# Servosolenoidvalve_of_Tatebayashi.net
KiCad netlist of a schematic drawn in EAGLE
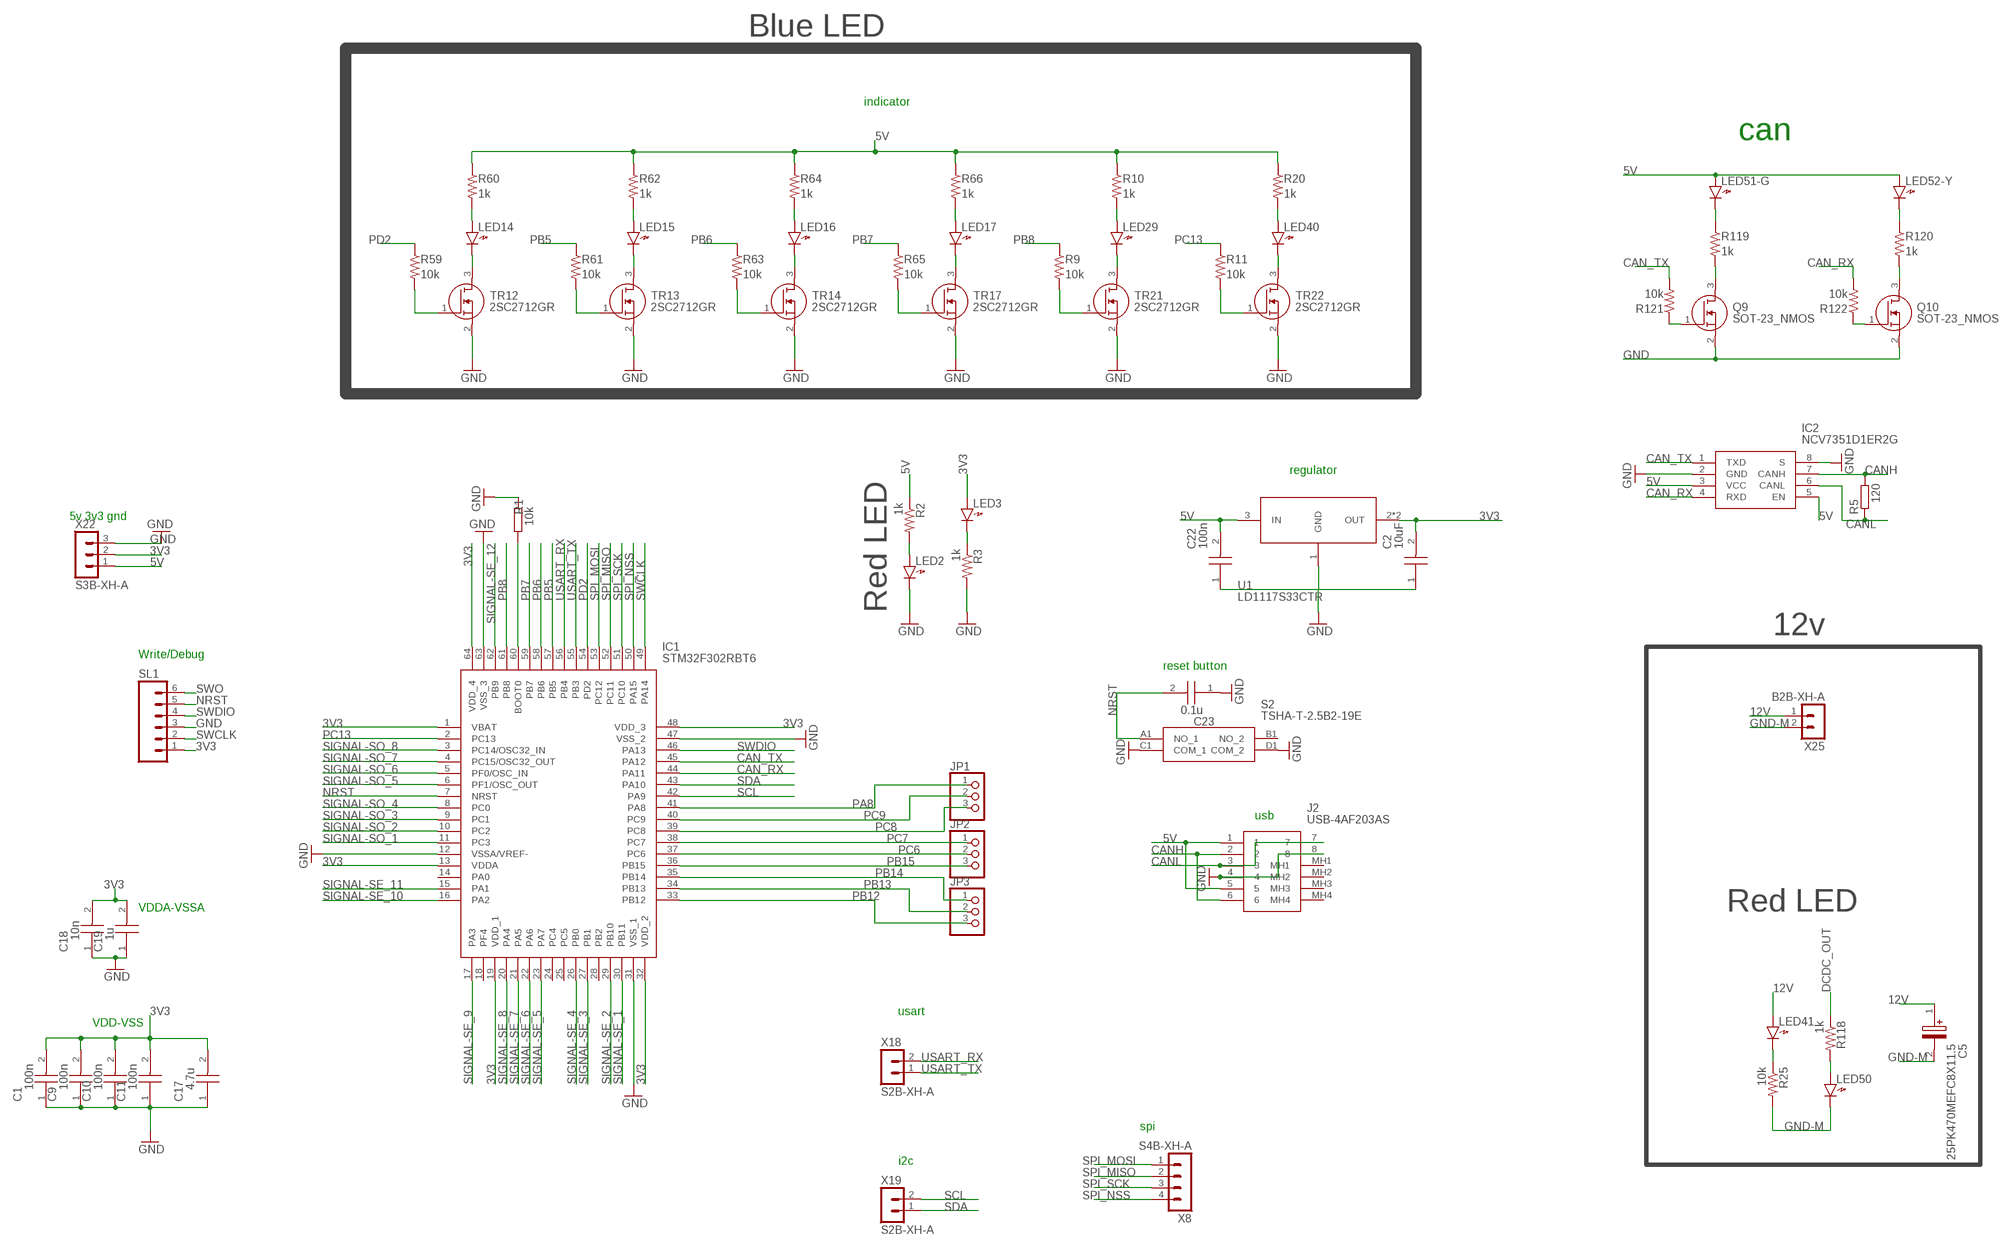
[diagram p0: schematic, sheet 1]
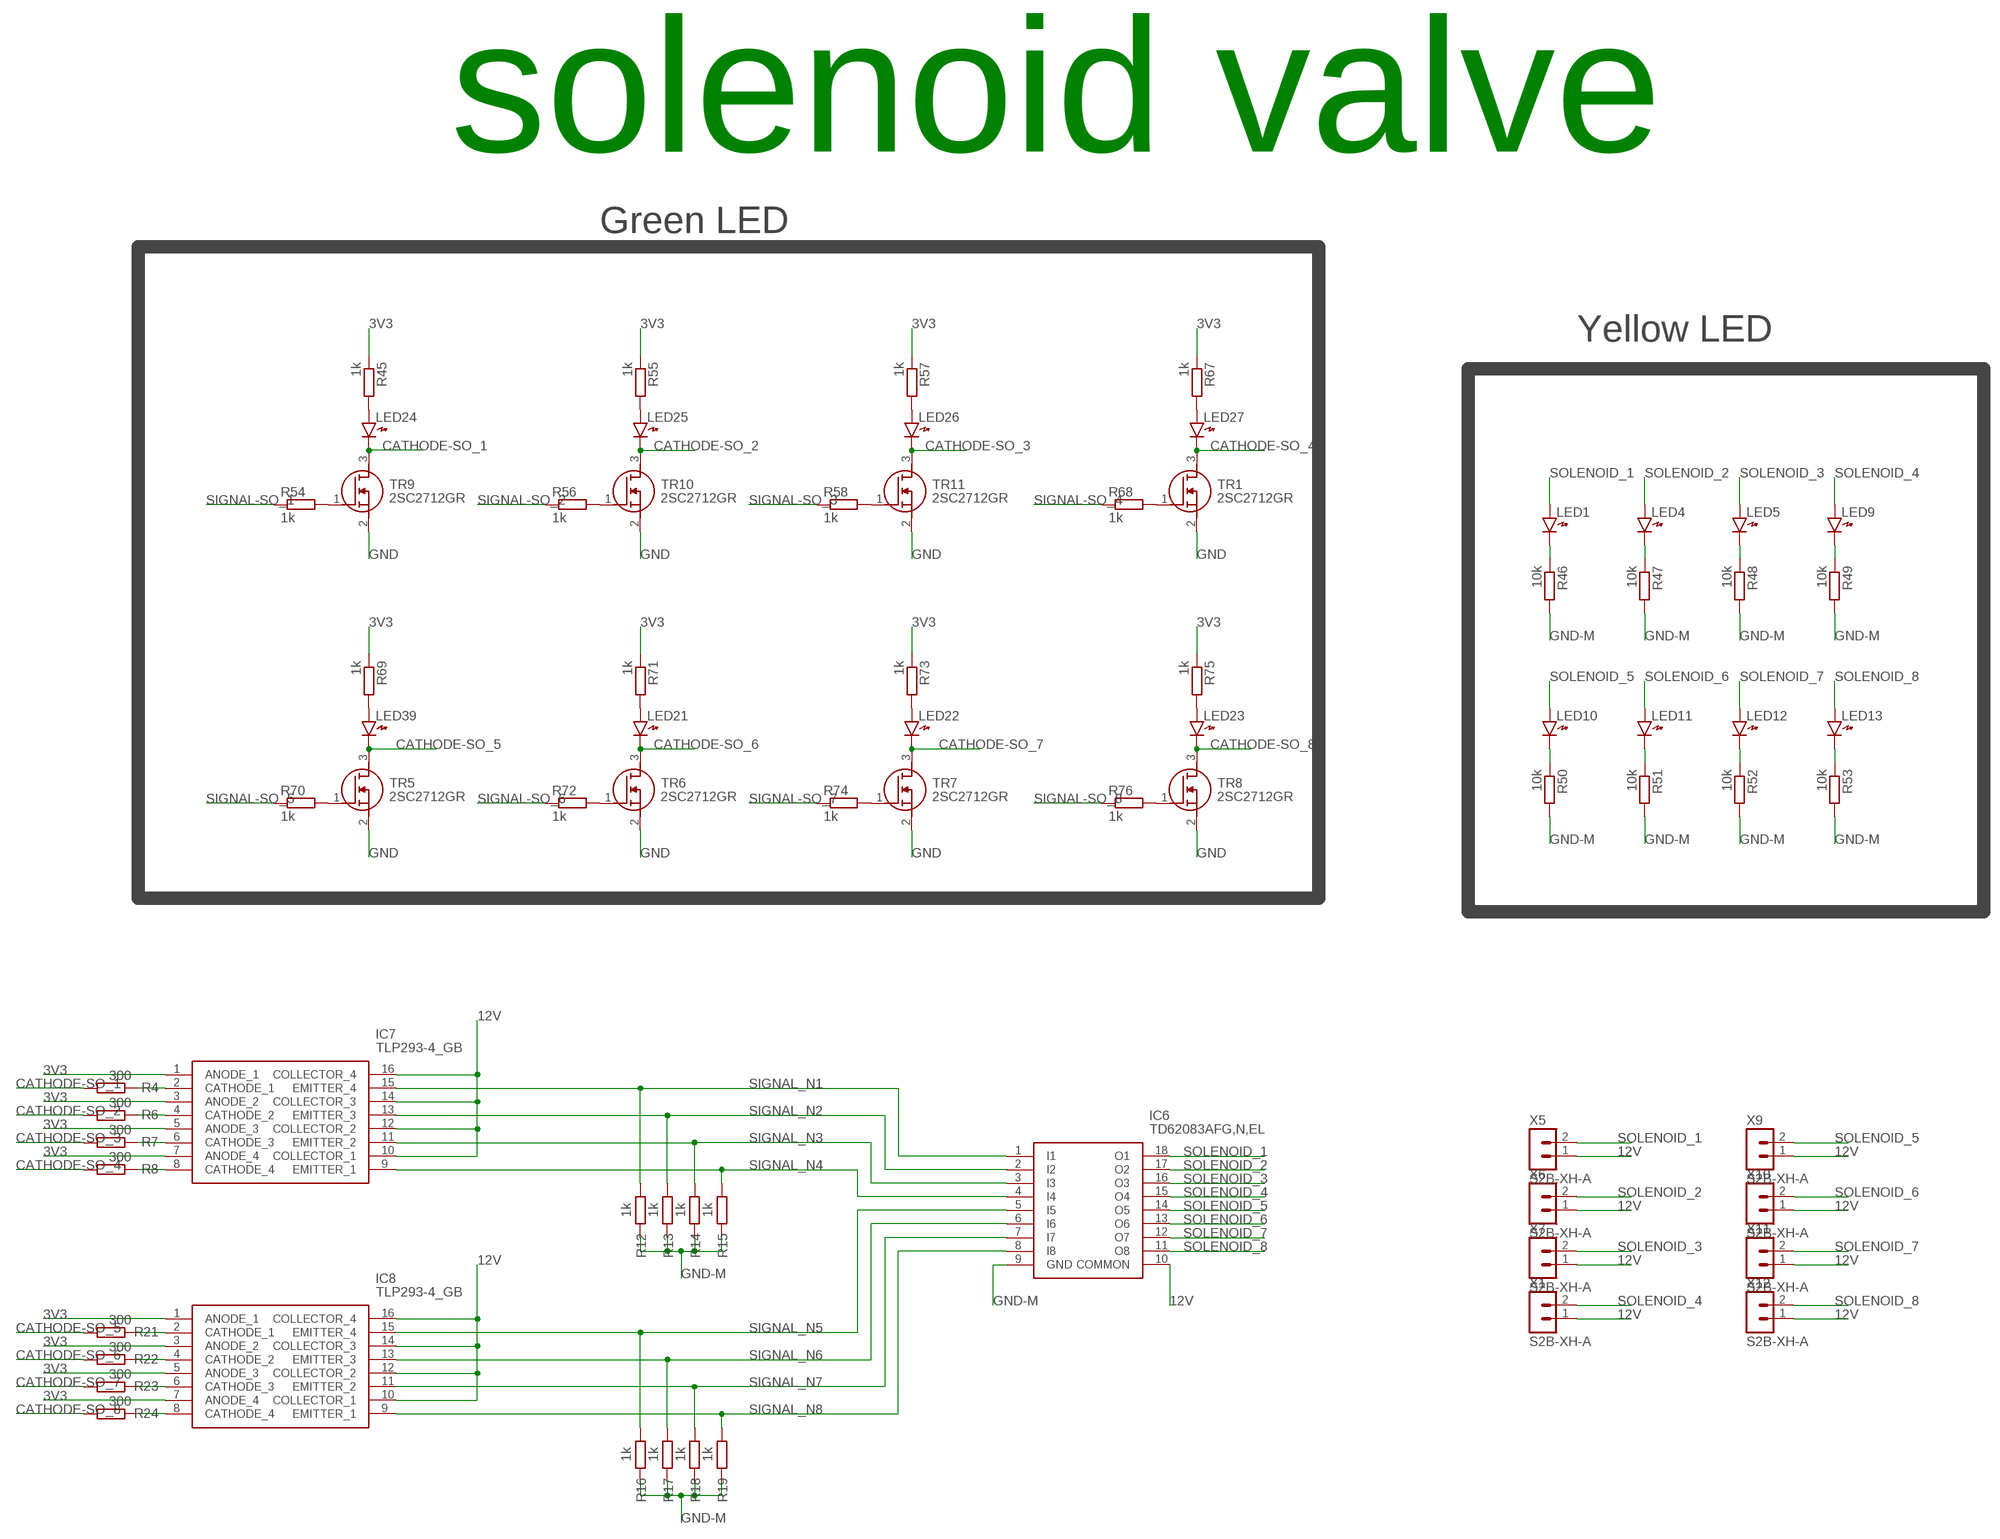
[diagram p1: schematic, sheet 2]
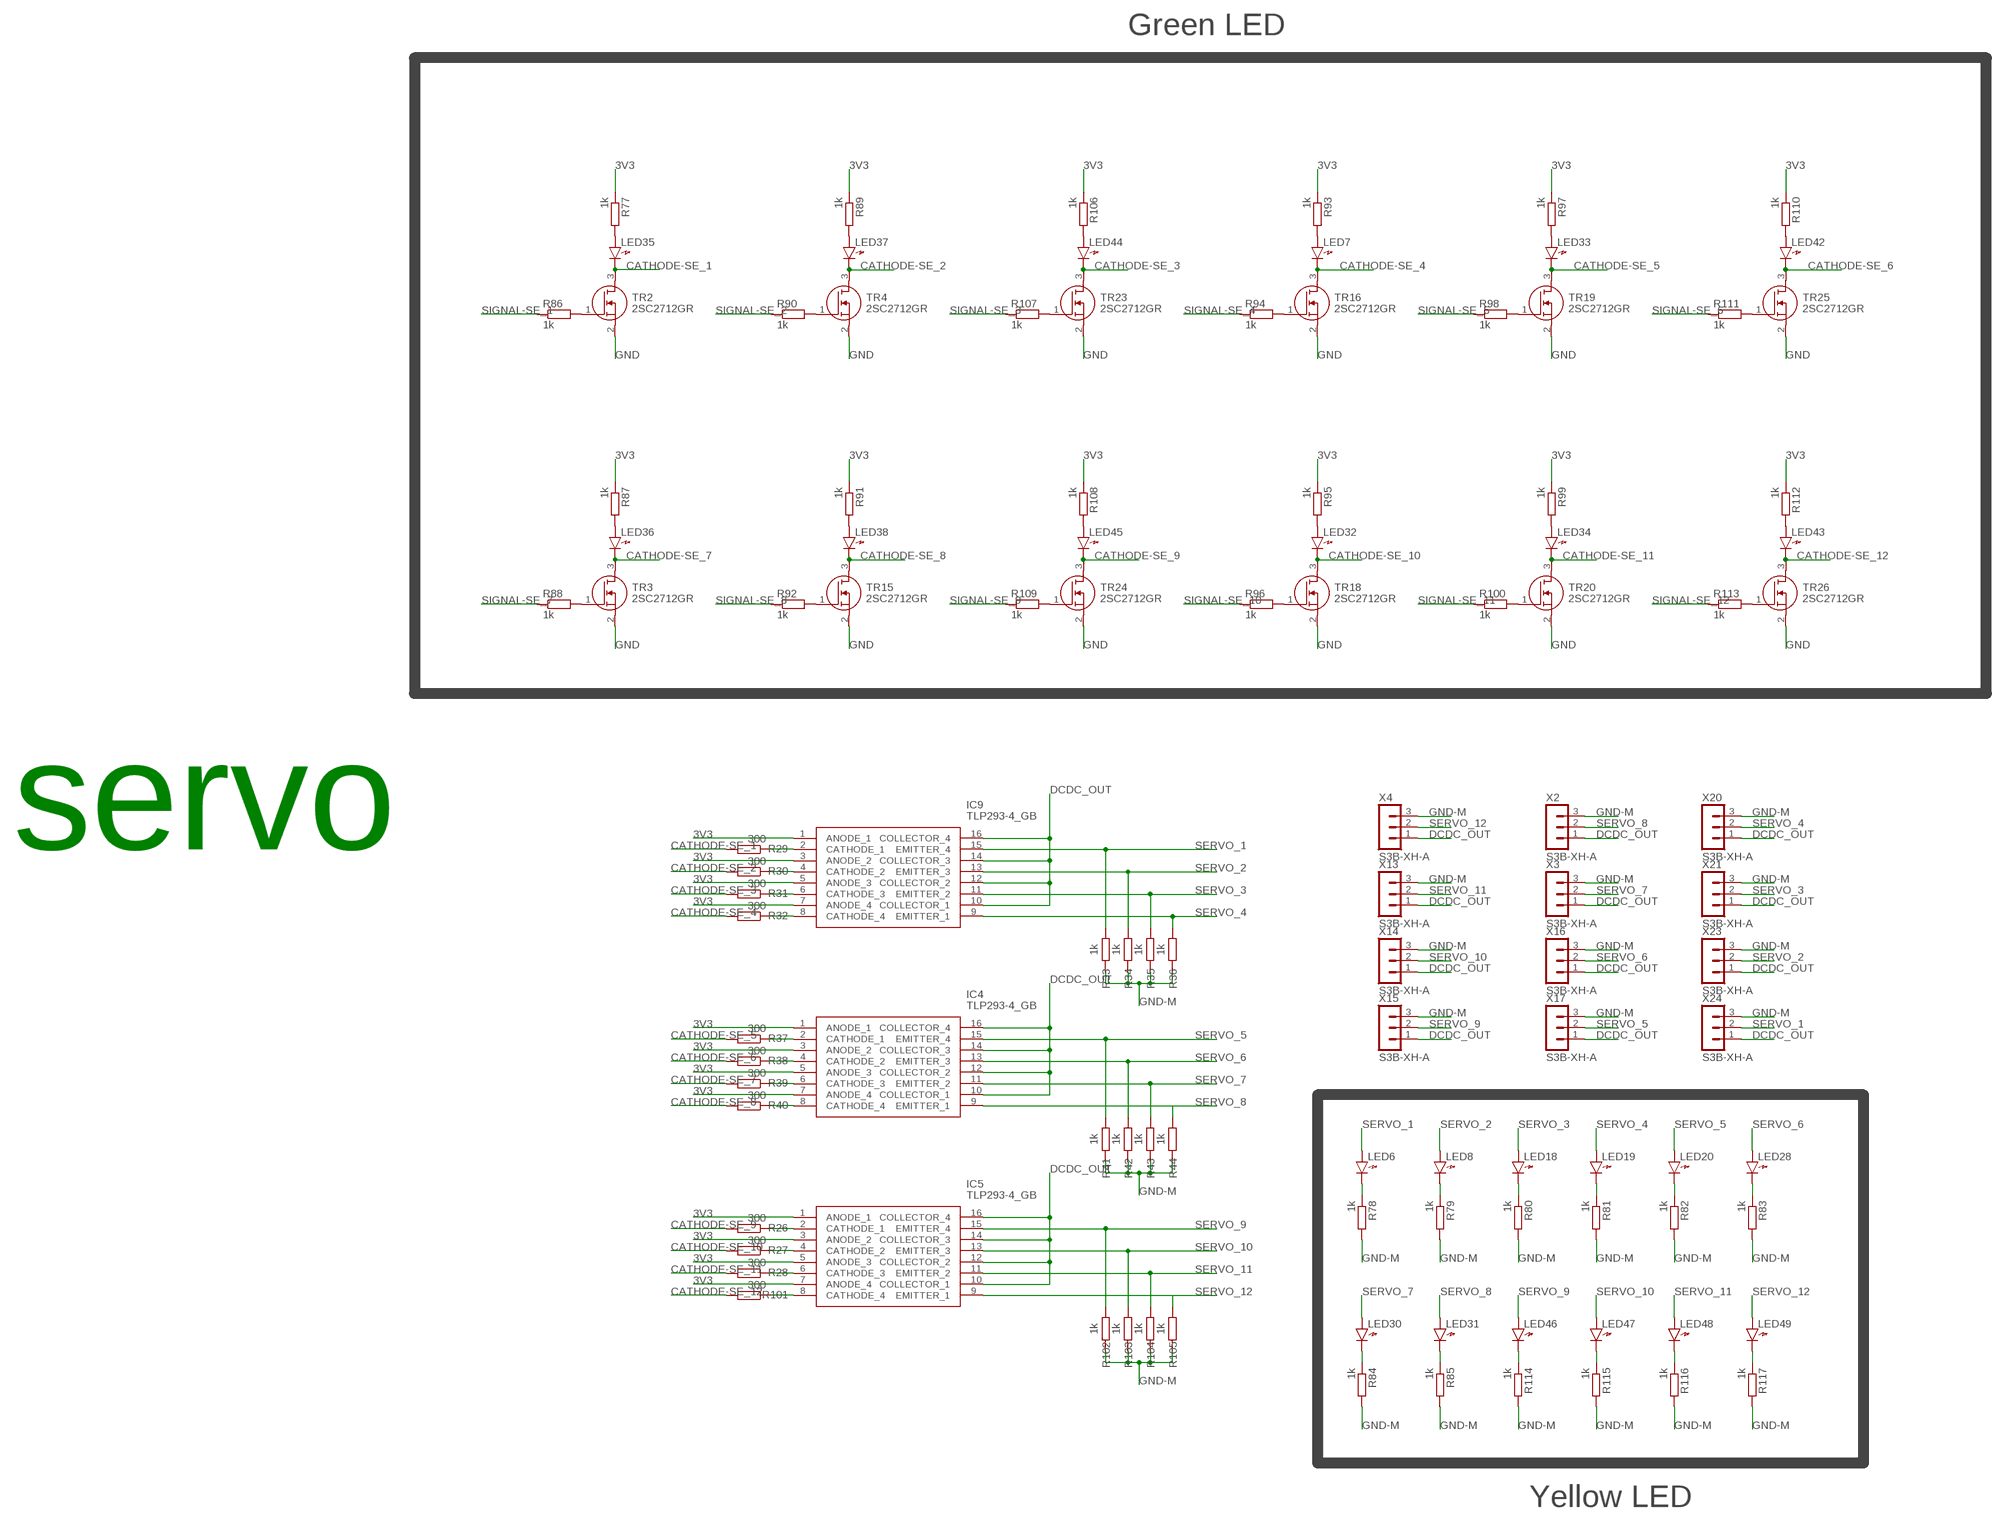
[diagram p2: schematic, sheet 3]

(export (version "E")
  (design (tool "Eeschema 10.0.6"))
  (components
    (comp (ref "IC6")
      (value "TD62083AFG,N,EL")
      (footprint "eagle-import:SOIC127P1030X245-18N")
      (libsource (lib "eagle-import") (part "TD62083AFG,N,EL"))
    )
    (comp (ref "IC7")
      (value "TLP293-4_GB")
      (footprint "eagle-import:SOP128P700X220-16N")
      (fields (field (name "MANUFACTURER_PART_NUMBER") "TLP293-4(GB"))
      (libsource (lib "eagle-import") (part "TLP293-4_GB"))
    )
    (comp (ref "IC8")
      (value "TLP293-4_GB")
      (footprint "eagle-import:SOP128P700X220-16N")
      (fields (field (name "MANUFACTURER_PART_NUMBER") "TLP293-4(GB"))
      (libsource (lib "eagle-import") (part "TLP293-4_GB"))
    )
    (comp (ref "LED1")
      (value "LED1608")
      (footprint "eagle-import:LED1608")
      (libsource (lib "eagle-import") (part "LED1608"))
    )
    (comp (ref "LED4")
      (value "LED1608")
      (footprint "eagle-import:LED1608")
      (libsource (lib "eagle-import") (part "LED1608"))
    )
    (comp (ref "LED5")
      (value "LED1608")
      (footprint "eagle-import:LED1608")
      (libsource (lib "eagle-import") (part "LED1608"))
    )
    (comp (ref "LED9")
      (value "LED1608")
      (footprint "eagle-import:LED1608")
      (libsource (lib "eagle-import") (part "LED1608"))
    )
    (comp (ref "LED10")
      (value "LED1608")
      (footprint "eagle-import:LED1608")
      (libsource (lib "eagle-import") (part "LED1608"))
    )
    (comp (ref "LED11")
      (value "LED1608")
      (footprint "eagle-import:LED1608")
      (libsource (lib "eagle-import") (part "LED1608"))
    )
    (comp (ref "LED12")
      (value "LED1608")
      (footprint "eagle-import:LED1608")
      (libsource (lib "eagle-import") (part "LED1608"))
    )
    (comp (ref "LED13")
      (value "LED1608")
      (footprint "eagle-import:LED1608")
      (libsource (lib "eagle-import") (part "LED1608"))
    )
    (comp (ref "LED21")
      (value "LED1608")
      (footprint "eagle-import:LED1608")
      (libsource (lib "eagle-import") (part "LED1608"))
    )
    (comp (ref "LED22")
      (value "LED1608")
      (footprint "eagle-import:LED1608")
      (libsource (lib "eagle-import") (part "LED1608"))
    )
    (comp (ref "LED23")
      (value "LED1608")
      (footprint "eagle-import:LED1608")
      (libsource (lib "eagle-import") (part "LED1608"))
    )
    (comp (ref "LED24")
      (value "LED1608")
      (footprint "eagle-import:LED1608")
      (libsource (lib "eagle-import") (part "LED1608"))
    )
    (comp (ref "LED25")
      (value "LED1608")
      (footprint "eagle-import:LED1608")
      (libsource (lib "eagle-import") (part "LED1608"))
    )
    (comp (ref "LED26")
      (value "LED1608")
      (footprint "eagle-import:LED1608")
      (libsource (lib "eagle-import") (part "LED1608"))
    )
    (comp (ref "LED27")
      (value "LED1608")
      (footprint "eagle-import:LED1608")
      (libsource (lib "eagle-import") (part "LED1608"))
    )
    (comp (ref "LED39")
      (value "LED1608")
      (footprint "eagle-import:LED1608")
      (libsource (lib "eagle-import") (part "LED1608"))
    )
    (comp (ref "R4")
      (value "300")
      (footprint "eagle-import:R0603")
      (libsource (lib "eagle-import") (part "R-EU_R0603"))
    )
    (comp (ref "R6")
      (value "300")
      (footprint "eagle-import:R0603")
      (libsource (lib "eagle-import") (part "R-EU_R0603"))
    )
    (comp (ref "R7")
      (value "300")
      (footprint "eagle-import:R0603")
      (libsource (lib "eagle-import") (part "R-EU_R0603"))
    )
    (comp (ref "R8")
      (value "300")
      (footprint "eagle-import:R0603")
      (libsource (lib "eagle-import") (part "R-EU_R0603"))
    )
    (comp (ref "R12")
      (value "1k")
      (footprint "eagle-import:R0603")
      (libsource (lib "eagle-import") (part "R-EU_R0603"))
    )
    (comp (ref "R13")
      (value "1k")
      (footprint "eagle-import:R0603")
      (libsource (lib "eagle-import") (part "R-EU_R0603"))
    )
    (comp (ref "R14")
      (value "1k")
      (footprint "eagle-import:R0603")
      (libsource (lib "eagle-import") (part "R-EU_R0603"))
    )
    (comp (ref "R15")
      (value "1k")
      (footprint "eagle-import:R0603")
      (libsource (lib "eagle-import") (part "R-EU_R0603"))
    )
    (comp (ref "R16")
      (value "1k")
      (footprint "eagle-import:R0603")
      (libsource (lib "eagle-import") (part "R-EU_R0603"))
    )
    (comp (ref "R17")
      (value "1k")
      (footprint "eagle-import:R0603")
      (libsource (lib "eagle-import") (part "R-EU_R0603"))
    )
    (comp (ref "R18")
      (value "1k")
      (footprint "eagle-import:R0603")
      (libsource (lib "eagle-import") (part "R-EU_R0603"))
    )
    (comp (ref "R19")
      (value "1k")
      (footprint "eagle-import:R0603")
      (libsource (lib "eagle-import") (part "R-EU_R0603"))
    )
    (comp (ref "R21")
      (value "300")
      (footprint "eagle-import:R0603")
      (libsource (lib "eagle-import") (part "R-EU_R0603"))
    )
    (comp (ref "R22")
      (value "300")
      (footprint "eagle-import:R0603")
      (libsource (lib "eagle-import") (part "R-EU_R0603"))
    )
    (comp (ref "R23")
      (value "300")
      (footprint "eagle-import:R0603")
      (libsource (lib "eagle-import") (part "R-EU_R0603"))
    )
    (comp (ref "R24")
      (value "300")
      (footprint "eagle-import:R0603")
      (libsource (lib "eagle-import") (part "R-EU_R0603"))
    )
    (comp (ref "R45")
      (value "1k")
      (footprint "eagle-import:R0603")
      (libsource (lib "eagle-import") (part "R-EU_R0603"))
    )
    (comp (ref "R46")
      (value "10k")
      (footprint "eagle-import:R0603")
      (libsource (lib "eagle-import") (part "R-EU_R0603"))
    )
    (comp (ref "R47")
      (value "10k")
      (footprint "eagle-import:R0603")
      (libsource (lib "eagle-import") (part "R-EU_R0603"))
    )
    (comp (ref "R48")
      (value "10k")
      (footprint "eagle-import:R0603")
      (libsource (lib "eagle-import") (part "R-EU_R0603"))
    )
    (comp (ref "R49")
      (value "10k")
      (footprint "eagle-import:R0603")
      (libsource (lib "eagle-import") (part "R-EU_R0603"))
    )
    (comp (ref "R50")
      (value "10k")
      (footprint "eagle-import:R0603")
      (libsource (lib "eagle-import") (part "R-EU_R0603"))
    )
    (comp (ref "R51")
      (value "10k")
      (footprint "eagle-import:R0603")
      (libsource (lib "eagle-import") (part "R-EU_R0603"))
    )
    (comp (ref "R52")
      (value "10k")
      (footprint "eagle-import:R0603")
      (libsource (lib "eagle-import") (part "R-EU_R0603"))
    )
    (comp (ref "R53")
      (value "10k")
      (footprint "eagle-import:R0603")
      (libsource (lib "eagle-import") (part "R-EU_R0603"))
    )
    (comp (ref "R54")
      (value "1k")
      (footprint "eagle-import:R0603")
      (libsource (lib "eagle-import") (part "R-EU_R0603"))
    )
    (comp (ref "R55")
      (value "1k")
      (footprint "eagle-import:R0603")
      (libsource (lib "eagle-import") (part "R-EU_R0603"))
    )
    (comp (ref "R56")
      (value "1k")
      (footprint "eagle-import:R0603")
      (libsource (lib "eagle-import") (part "R-EU_R0603"))
    )
    (comp (ref "R57")
      (value "1k")
      (footprint "eagle-import:R0603")
      (libsource (lib "eagle-import") (part "R-EU_R0603"))
    )
    (comp (ref "R58")
      (value "1k")
      (footprint "eagle-import:R0603")
      (libsource (lib "eagle-import") (part "R-EU_R0603"))
    )
    (comp (ref "R67")
      (value "1k")
      (footprint "eagle-import:R0603")
      (libsource (lib "eagle-import") (part "R-EU_R0603"))
    )
    (comp (ref "R68")
      (value "1k")
      (footprint "eagle-import:R0603")
      (libsource (lib "eagle-import") (part "R-EU_R0603"))
    )
    (comp (ref "R69")
      (value "1k")
      (footprint "eagle-import:R0603")
      (libsource (lib "eagle-import") (part "R-EU_R0603"))
    )
    (comp (ref "R70")
      (value "1k")
      (footprint "eagle-import:R0603")
      (libsource (lib "eagle-import") (part "R-EU_R0603"))
    )
    (comp (ref "R71")
      (value "1k")
      (footprint "eagle-import:R0603")
      (libsource (lib "eagle-import") (part "R-EU_R0603"))
    )
    (comp (ref "R72")
      (value "1k")
      (footprint "eagle-import:R0603")
      (libsource (lib "eagle-import") (part "R-EU_R0603"))
    )
    (comp (ref "R73")
      (value "1k")
      (footprint "eagle-import:R0603")
      (libsource (lib "eagle-import") (part "R-EU_R0603"))
    )
    (comp (ref "R74")
      (value "1k")
      (footprint "eagle-import:R0603")
      (libsource (lib "eagle-import") (part "R-EU_R0603"))
    )
    (comp (ref "R75")
      (value "1k")
      (footprint "eagle-import:R0603")
      (libsource (lib "eagle-import") (part "R-EU_R0603"))
    )
    (comp (ref "R76")
      (value "1k")
      (footprint "eagle-import:R0603")
      (libsource (lib "eagle-import") (part "R-EU_R0603"))
    )
    (comp (ref "TR1")
      (value "2SC2712GR")
      (footprint "eagle-import:SOT-23")
      (libsource (lib "eagle-import") (part "SOT-23_NMOS"))
    )
    (comp (ref "TR5")
      (value "2SC2712GR")
      (footprint "eagle-import:SOT-23")
      (libsource (lib "eagle-import") (part "SOT-23_NMOS"))
    )
    (comp (ref "TR6")
      (value "2SC2712GR")
      (footprint "eagle-import:SOT-23")
      (libsource (lib "eagle-import") (part "SOT-23_NMOS"))
    )
    (comp (ref "TR7")
      (value "2SC2712GR")
      (footprint "eagle-import:SOT-23")
      (libsource (lib "eagle-import") (part "SOT-23_NMOS"))
    )
    (comp (ref "TR8")
      (value "2SC2712GR")
      (footprint "eagle-import:SOT-23")
      (libsource (lib "eagle-import") (part "SOT-23_NMOS"))
    )
    (comp (ref "TR9")
      (value "2SC2712GR")
      (footprint "eagle-import:SOT-23")
      (libsource (lib "eagle-import") (part "SOT-23_NMOS"))
    )
    (comp (ref "TR10")
      (value "2SC2712GR")
      (footprint "eagle-import:SOT-23")
      (libsource (lib "eagle-import") (part "SOT-23_NMOS"))
    )
    (comp (ref "TR11")
      (value "2SC2712GR")
      (footprint "eagle-import:SOT-23")
      (libsource (lib "eagle-import") (part "SOT-23_NMOS"))
    )
    (comp (ref "X1")
      (value "S2B-XH-A")
      (footprint "eagle-import:S2B-XH-A")
      (libsource (lib "eagle-import") (part "S2B-XH-A"))
    )
    (comp (ref "X5")
      (value "S2B-XH-A")
      (footprint "eagle-import:S2B-XH-A")
      (libsource (lib "eagle-import") (part "S2B-XH-A"))
    )
    (comp (ref "X6")
      (value "S2B-XH-A")
      (footprint "eagle-import:S2B-XH-A")
      (libsource (lib "eagle-import") (part "S2B-XH-A"))
    )
    (comp (ref "X7")
      (value "S2B-XH-A")
      (footprint "eagle-import:S2B-XH-A")
      (libsource (lib "eagle-import") (part "S2B-XH-A"))
    )
    (comp (ref "X9")
      (value "S2B-XH-A")
      (footprint "eagle-import:S2B-XH-A")
      (libsource (lib "eagle-import") (part "S2B-XH-A"))
    )
    (comp (ref "X10")
      (value "S2B-XH-A")
      (footprint "eagle-import:S2B-XH-A")
      (libsource (lib "eagle-import") (part "S2B-XH-A"))
    )
    (comp (ref "X11")
      (value "S2B-XH-A")
      (footprint "eagle-import:S2B-XH-A")
      (libsource (lib "eagle-import") (part "S2B-XH-A"))
    )
    (comp (ref "X12")
      (value "S2B-XH-A")
      (footprint "eagle-import:S2B-XH-A")
      (libsource (lib "eagle-import") (part "S2B-XH-A"))
    )
    (comp (ref "IC4")
      (value "TLP293-4_GB")
      (footprint "eagle-import:SOP128P700X220-16N")
      (fields (field (name "MANUFACTURER_PART_NUMBER") "TLP293-4(GB"))
      (libsource (lib "eagle-import") (part "TLP293-4_GB"))
    )
    (comp (ref "IC5")
      (value "TLP293-4_GB")
      (footprint "eagle-import:SOP128P700X220-16N")
      (fields (field (name "MANUFACTURER_PART_NUMBER") "TLP293-4(GB"))
      (libsource (lib "eagle-import") (part "TLP293-4_GB"))
    )
    (comp (ref "IC9")
      (value "TLP293-4_GB")
      (footprint "eagle-import:SOP128P700X220-16N")
      (fields (field (name "MANUFACTURER_PART_NUMBER") "TLP293-4(GB"))
      (libsource (lib "eagle-import") (part "TLP293-4_GB"))
    )
    (comp (ref "LED6")
      (value "LED1608")
      (footprint "eagle-import:LED1608")
      (libsource (lib "eagle-import") (part "LED1608"))
    )
    (comp (ref "LED7")
      (value "LED1608")
      (footprint "eagle-import:LED1608")
      (libsource (lib "eagle-import") (part "LED1608"))
    )
    (comp (ref "LED8")
      (value "LED1608")
      (footprint "eagle-import:LED1608")
      (libsource (lib "eagle-import") (part "LED1608"))
    )
    (comp (ref "LED18")
      (value "LED1608")
      (footprint "eagle-import:LED1608")
      (libsource (lib "eagle-import") (part "LED1608"))
    )
    (comp (ref "LED19")
      (value "LED1608")
      (footprint "eagle-import:LED1608")
      (libsource (lib "eagle-import") (part "LED1608"))
    )
    (comp (ref "LED20")
      (value "LED1608")
      (footprint "eagle-import:LED1608")
      (libsource (lib "eagle-import") (part "LED1608"))
    )
    (comp (ref "LED28")
      (value "LED1608")
      (footprint "eagle-import:LED1608")
      (libsource (lib "eagle-import") (part "LED1608"))
    )
    (comp (ref "LED30")
      (value "LED1608")
      (footprint "eagle-import:LED1608")
      (libsource (lib "eagle-import") (part "LED1608"))
    )
    (comp (ref "LED31")
      (value "LED1608")
      (footprint "eagle-import:LED1608")
      (libsource (lib "eagle-import") (part "LED1608"))
    )
    (comp (ref "LED32")
      (value "LED1608")
      (footprint "eagle-import:LED1608")
      (libsource (lib "eagle-import") (part "LED1608"))
    )
    (comp (ref "LED33")
      (value "LED1608")
      (footprint "eagle-import:LED1608")
      (libsource (lib "eagle-import") (part "LED1608"))
    )
    (comp (ref "LED34")
      (value "LED1608")
      (footprint "eagle-import:LED1608")
      (libsource (lib "eagle-import") (part "LED1608"))
    )
    (comp (ref "LED35")
      (value "LED1608")
      (footprint "eagle-import:LED1608")
      (libsource (lib "eagle-import") (part "LED1608"))
    )
    (comp (ref "LED36")
      (value "LED1608")
      (footprint "eagle-import:LED1608")
      (libsource (lib "eagle-import") (part "LED1608"))
    )
    (comp (ref "LED37")
      (value "LED1608")
      (footprint "eagle-import:LED1608")
      (libsource (lib "eagle-import") (part "LED1608"))
    )
    (comp (ref "LED38")
      (value "LED1608")
      (footprint "eagle-import:LED1608")
      (libsource (lib "eagle-import") (part "LED1608"))
    )
    (comp (ref "LED42")
      (value "LED1608")
      (footprint "eagle-import:LED1608")
      (libsource (lib "eagle-import") (part "LED1608"))
    )
    (comp (ref "LED43")
      (value "LED1608")
      (footprint "eagle-import:LED1608")
      (libsource (lib "eagle-import") (part "LED1608"))
    )
    (comp (ref "LED44")
      (value "LED1608")
      (footprint "eagle-import:LED1608")
      (libsource (lib "eagle-import") (part "LED1608"))
    )
    (comp (ref "LED45")
      (value "LED1608")
      (footprint "eagle-import:LED1608")
      (libsource (lib "eagle-import") (part "LED1608"))
    )
    (comp (ref "LED46")
      (value "LED1608")
      (footprint "eagle-import:LED1608")
      (libsource (lib "eagle-import") (part "LED1608"))
    )
    (comp (ref "LED47")
      (value "LED1608")
      (footprint "eagle-import:LED1608")
      (libsource (lib "eagle-import") (part "LED1608"))
    )
    (comp (ref "LED48")
      (value "LED1608")
      (footprint "eagle-import:LED1608")
      (libsource (lib "eagle-import") (part "LED1608"))
    )
    (comp (ref "LED49")
      (value "LED1608")
      (footprint "eagle-import:LED1608")
      (libsource (lib "eagle-import") (part "LED1608"))
    )
    (comp (ref "R26")
      (value "300")
      (footprint "eagle-import:R0603")
      (libsource (lib "eagle-import") (part "R-EU_R0603"))
    )
    (comp (ref "R27")
      (value "300")
      (footprint "eagle-import:R0603")
      (libsource (lib "eagle-import") (part "R-EU_R0603"))
    )
    (comp (ref "R28")
      (value "300")
      (footprint "eagle-import:R0603")
      (libsource (lib "eagle-import") (part "R-EU_R0603"))
    )
    (comp (ref "R29")
      (value "300")
      (footprint "eagle-import:R0603")
      (libsource (lib "eagle-import") (part "R-EU_R0603"))
    )
    (comp (ref "R30")
      (value "300")
      (footprint "eagle-import:R0603")
      (libsource (lib "eagle-import") (part "R-EU_R0603"))
    )
    (comp (ref "R31")
      (value "300")
      (footprint "eagle-import:R0603")
      (libsource (lib "eagle-import") (part "R-EU_R0603"))
    )
    (comp (ref "R32")
      (value "300")
      (footprint "eagle-import:R0603")
      (libsource (lib "eagle-import") (part "R-EU_R0603"))
    )
    (comp (ref "R33")
      (value "1k")
      (footprint "eagle-import:R0603")
      (libsource (lib "eagle-import") (part "R-EU_R0603"))
    )
    (comp (ref "R34")
      (value "1k")
      (footprint "eagle-import:R0603")
      (libsource (lib "eagle-import") (part "R-EU_R0603"))
    )
    (comp (ref "R35")
      (value "1k")
      (footprint "eagle-import:R0603")
      (libsource (lib "eagle-import") (part "R-EU_R0603"))
    )
    (comp (ref "R36")
      (value "1k")
      (footprint "eagle-import:R0603")
      (libsource (lib "eagle-import") (part "R-EU_R0603"))
    )
    (comp (ref "R37")
      (value "300")
      (footprint "eagle-import:R0603")
      (libsource (lib "eagle-import") (part "R-EU_R0603"))
    )
    (comp (ref "R38")
      (value "300")
      (footprint "eagle-import:R0603")
      (libsource (lib "eagle-import") (part "R-EU_R0603"))
    )
    (comp (ref "R39")
      (value "300")
      (footprint "eagle-import:R0603")
      (libsource (lib "eagle-import") (part "R-EU_R0603"))
    )
    (comp (ref "R40")
      (value "300")
      (footprint "eagle-import:R0603")
      (libsource (lib "eagle-import") (part "R-EU_R0603"))
    )
    (comp (ref "R41")
      (value "1k")
      (footprint "eagle-import:R0603")
      (libsource (lib "eagle-import") (part "R-EU_R0603"))
    )
    (comp (ref "R42")
      (value "1k")
      (footprint "eagle-import:R0603")
      (libsource (lib "eagle-import") (part "R-EU_R0603"))
    )
    (comp (ref "R43")
      (value "1k")
      (footprint "eagle-import:R0603")
      (libsource (lib "eagle-import") (part "R-EU_R0603"))
    )
    (comp (ref "R44")
      (value "1k")
      (footprint "eagle-import:R0603")
      (libsource (lib "eagle-import") (part "R-EU_R0603"))
    )
    (comp (ref "R77")
      (value "1k")
      (footprint "eagle-import:R0603")
      (libsource (lib "eagle-import") (part "R-EU_R0603"))
    )
    (comp (ref "R78")
      (value "1k")
      (footprint "eagle-import:R0603")
      (libsource (lib "eagle-import") (part "R-EU_R0603"))
    )
    (comp (ref "R79")
      (value "1k")
      (footprint "eagle-import:R0603")
      (libsource (lib "eagle-import") (part "R-EU_R0603"))
    )
    (comp (ref "R80")
      (value "1k")
      (footprint "eagle-import:R0603")
      (libsource (lib "eagle-import") (part "R-EU_R0603"))
    )
    (comp (ref "R81")
      (value "1k")
      (footprint "eagle-import:R0603")
      (libsource (lib "eagle-import") (part "R-EU_R0603"))
    )
    (comp (ref "R82")
      (value "1k")
      (footprint "eagle-import:R0603")
      (libsource (lib "eagle-import") (part "R-EU_R0603"))
    )
    (comp (ref "R83")
      (value "1k")
      (footprint "eagle-import:R0603")
      (libsource (lib "eagle-import") (part "R-EU_R0603"))
    )
    (comp (ref "R84")
      (value "1k")
      (footprint "eagle-import:R0603")
      (libsource (lib "eagle-import") (part "R-EU_R0603"))
    )
    (comp (ref "R85")
      (value "1k")
      (footprint "eagle-import:R0603")
      (libsource (lib "eagle-import") (part "R-EU_R0603"))
    )
    (comp (ref "R86")
      (value "1k")
      (footprint "eagle-import:R0603")
      (libsource (lib "eagle-import") (part "R-EU_R0603"))
    )
    (comp (ref "R87")
      (value "1k")
      (footprint "eagle-import:R0603")
      (libsource (lib "eagle-import") (part "R-EU_R0603"))
    )
    (comp (ref "R88")
      (value "1k")
      (footprint "eagle-import:R0603")
      (libsource (lib "eagle-import") (part "R-EU_R0603"))
    )
    (comp (ref "R89")
      (value "1k")
      (footprint "eagle-import:R0603")
      (libsource (lib "eagle-import") (part "R-EU_R0603"))
    )
    (comp (ref "R90")
      (value "1k")
      (footprint "eagle-import:R0603")
      (libsource (lib "eagle-import") (part "R-EU_R0603"))
    )
    (comp (ref "R91")
      (value "1k")
      (footprint "eagle-import:R0603")
      (libsource (lib "eagle-import") (part "R-EU_R0603"))
    )
    (comp (ref "R92")
      (value "1k")
      (footprint "eagle-import:R0603")
      (libsource (lib "eagle-import") (part "R-EU_R0603"))
    )
    (comp (ref "R93")
      (value "1k")
      (footprint "eagle-import:R0603")
      (libsource (lib "eagle-import") (part "R-EU_R0603"))
    )
    (comp (ref "R94")
      (value "1k")
      (footprint "eagle-import:R0603")
      (libsource (lib "eagle-import") (part "R-EU_R0603"))
    )
    (comp (ref "R95")
      (value "1k")
      (footprint "eagle-import:R0603")
      (libsource (lib "eagle-import") (part "R-EU_R0603"))
    )
    (comp (ref "R96")
      (value "1k")
      (footprint "eagle-import:R0603")
      (libsource (lib "eagle-import") (part "R-EU_R0603"))
    )
    (comp (ref "R97")
      (value "1k")
      (footprint "eagle-import:R0603")
      (libsource (lib "eagle-import") (part "R-EU_R0603"))
    )
    (comp (ref "R98")
      (value "1k")
      (footprint "eagle-import:R0603")
      (libsource (lib "eagle-import") (part "R-EU_R0603"))
    )
    (comp (ref "R99")
      (value "1k")
      (footprint "eagle-import:R0603")
      (libsource (lib "eagle-import") (part "R-EU_R0603"))
    )
    (comp (ref "R100")
      (value "1k")
      (footprint "eagle-import:R0603")
      (libsource (lib "eagle-import") (part "R-EU_R0603"))
    )
    (comp (ref "R101")
      (value "300")
      (footprint "eagle-import:R0603")
      (libsource (lib "eagle-import") (part "R-EU_R0603"))
    )
    (comp (ref "R102")
      (value "1k")
      (footprint "eagle-import:R0603")
      (libsource (lib "eagle-import") (part "R-EU_R0603"))
    )
    (comp (ref "R103")
      (value "1k")
      (footprint "eagle-import:R0603")
      (libsource (lib "eagle-import") (part "R-EU_R0603"))
    )
    (comp (ref "R104")
      (value "1k")
      (footprint "eagle-import:R0603")
      (libsource (lib "eagle-import") (part "R-EU_R0603"))
    )
    (comp (ref "R105")
      (value "1k")
      (footprint "eagle-import:R0603")
      (libsource (lib "eagle-import") (part "R-EU_R0603"))
    )
    (comp (ref "R106")
      (value "1k")
      (footprint "eagle-import:R0603")
      (libsource (lib "eagle-import") (part "R-EU_R0603"))
    )
    (comp (ref "R107")
      (value "1k")
      (footprint "eagle-import:R0603")
      (libsource (lib "eagle-import") (part "R-EU_R0603"))
    )
    (comp (ref "R108")
      (value "1k")
      (footprint "eagle-import:R0603")
      (libsource (lib "eagle-import") (part "R-EU_R0603"))
    )
    (comp (ref "R109")
      (value "1k")
      (footprint "eagle-import:R0603")
      (libsource (lib "eagle-import") (part "R-EU_R0603"))
    )
    (comp (ref "R110")
      (value "1k")
      (footprint "eagle-import:R0603")
      (libsource (lib "eagle-import") (part "R-EU_R0603"))
    )
    (comp (ref "R111")
      (value "1k")
      (footprint "eagle-import:R0603")
      (libsource (lib "eagle-import") (part "R-EU_R0603"))
    )
    (comp (ref "R112")
      (value "1k")
      (footprint "eagle-import:R0603")
      (libsource (lib "eagle-import") (part "R-EU_R0603"))
    )
    (comp (ref "R113")
      (value "1k")
      (footprint "eagle-import:R0603")
      (libsource (lib "eagle-import") (part "R-EU_R0603"))
    )
    (comp (ref "R114")
      (value "1k")
      (footprint "eagle-import:R0603")
      (libsource (lib "eagle-import") (part "R-EU_R0603"))
    )
    (comp (ref "R115")
      (value "1k")
      (footprint "eagle-import:R0603")
      (libsource (lib "eagle-import") (part "R-EU_R0603"))
    )
    (comp (ref "R116")
      (value "1k")
      (footprint "eagle-import:R0603")
      (libsource (lib "eagle-import") (part "R-EU_R0603"))
    )
    (comp (ref "R117")
      (value "1k")
      (footprint "eagle-import:R0603")
      (libsource (lib "eagle-import") (part "R-EU_R0603"))
    )
    (comp (ref "TR2")
      (value "2SC2712GR")
      (footprint "eagle-import:SOT-23")
      (libsource (lib "eagle-import") (part "SOT-23_NMOS"))
    )
    (comp (ref "TR3")
      (value "2SC2712GR")
      (footprint "eagle-import:SOT-23")
      (libsource (lib "eagle-import") (part "SOT-23_NMOS"))
    )
    (comp (ref "TR4")
      (value "2SC2712GR")
      (footprint "eagle-import:SOT-23")
      (libsource (lib "eagle-import") (part "SOT-23_NMOS"))
    )
    (comp (ref "TR15")
      (value "2SC2712GR")
      (footprint "eagle-import:SOT-23")
      (libsource (lib "eagle-import") (part "SOT-23_NMOS"))
    )
    (comp (ref "TR16")
      (value "2SC2712GR")
      (footprint "eagle-import:SOT-23")
      (libsource (lib "eagle-import") (part "SOT-23_NMOS"))
    )
    (comp (ref "TR18")
      (value "2SC2712GR")
      (footprint "eagle-import:SOT-23")
      (libsource (lib "eagle-import") (part "SOT-23_NMOS"))
    )
    (comp (ref "TR19")
      (value "2SC2712GR")
      (footprint "eagle-import:SOT-23")
      (libsource (lib "eagle-import") (part "SOT-23_NMOS"))
    )
    (comp (ref "TR20")
      (value "2SC2712GR")
      (footprint "eagle-import:SOT-23")
      (libsource (lib "eagle-import") (part "SOT-23_NMOS"))
    )
    (comp (ref "TR23")
      (value "2SC2712GR")
      (footprint "eagle-import:SOT-23")
      (libsource (lib "eagle-import") (part "SOT-23_NMOS"))
    )
    (comp (ref "TR24")
      (value "2SC2712GR")
      (footprint "eagle-import:SOT-23")
      (libsource (lib "eagle-import") (part "SOT-23_NMOS"))
    )
    (comp (ref "TR25")
      (value "2SC2712GR")
      (footprint "eagle-import:SOT-23")
      (libsource (lib "eagle-import") (part "SOT-23_NMOS"))
    )
    (comp (ref "TR26")
      (value "2SC2712GR")
      (footprint "eagle-import:SOT-23")
      (libsource (lib "eagle-import") (part "SOT-23_NMOS"))
    )
    (comp (ref "X2")
      (value "S3B-XH-A")
      (footprint "eagle-import:S3B-XH-A")
      (libsource (lib "eagle-import") (part "S3B-XH-A"))
    )
    (comp (ref "X3")
      (value "S3B-XH-A")
      (footprint "eagle-import:S3B-XH-A")
      (libsource (lib "eagle-import") (part "S3B-XH-A"))
    )
    (comp (ref "X4")
      (value "S3B-XH-A")
      (footprint "eagle-import:S3B-XH-A")
      (libsource (lib "eagle-import") (part "S3B-XH-A"))
    )
    (comp (ref "X13")
      (value "S3B-XH-A")
      (footprint "eagle-import:S3B-XH-A")
      (libsource (lib "eagle-import") (part "S3B-XH-A"))
    )
    (comp (ref "X14")
      (value "S3B-XH-A")
      (footprint "eagle-import:S3B-XH-A")
      (libsource (lib "eagle-import") (part "S3B-XH-A"))
    )
    (comp (ref "X15")
      (value "S3B-XH-A")
      (footprint "eagle-import:S3B-XH-A")
      (libsource (lib "eagle-import") (part "S3B-XH-A"))
    )
    (comp (ref "X16")
      (value "S3B-XH-A")
      (footprint "eagle-import:S3B-XH-A")
      (libsource (lib "eagle-import") (part "S3B-XH-A"))
    )
    (comp (ref "X17")
      (value "S3B-XH-A")
      (footprint "eagle-import:S3B-XH-A")
      (libsource (lib "eagle-import") (part "S3B-XH-A"))
    )
    (comp (ref "X20")
      (value "S3B-XH-A")
      (footprint "eagle-import:S3B-XH-A")
      (libsource (lib "eagle-import") (part "S3B-XH-A"))
    )
    (comp (ref "X21")
      (value "S3B-XH-A")
      (footprint "eagle-import:S3B-XH-A")
      (libsource (lib "eagle-import") (part "S3B-XH-A"))
    )
    (comp (ref "X23")
      (value "S3B-XH-A")
      (footprint "eagle-import:S3B-XH-A")
      (libsource (lib "eagle-import") (part "S3B-XH-A"))
    )
    (comp (ref "X24")
      (value "S3B-XH-A")
      (footprint "eagle-import:S3B-XH-A")
      (libsource (lib "eagle-import") (part "S3B-XH-A"))
    )
    (comp (ref "C1")
      (value "100n")
      (footprint "eagle-import:CAPC1709X100N")
      (fields
        (field (name "MANUFACTURER_PART_NUMBER") "AMK107BBJ476MA-RE")
        (field (name "MOUSER_PART_NUMBER") "963-AMK107BBJ476MARE")
        (field (name "RS_PART_NUMBER") "1843762P")
      )
      (libsource (lib "eagle-import") (part "AMK107BBJ476MA-RE"))
    )
    (comp (ref "C2")
      (value "10uF")
      (footprint "eagle-import:CAPC1608X90N")
      (fields
        (field (name "MANUFACTURER_PART_NUMBER") "GRM188B31A106KE69D")
        (field (name "RS_PART_NUMBER") "8847157P")
      )
      (libsource (lib "eagle-import") (part "GRM188B31A106KE69D"))
    )
    (comp (ref "C5")
      (value "25PK470MEFC8X11.5")
      (footprint "eagle-import:CAPPRD350W60D825H1150")
      (fields (field (name "MOUSER_PART_NUMBER") "232-25PK470MEFC8X115"))
      (libsource (lib "eagle-import") (part "25PK470MEFC8X11.5"))
    )
    (comp (ref "C9")
      (value "100n")
      (footprint "eagle-import:CAPC1709X100N")
      (fields
        (field (name "MANUFACTURER_PART_NUMBER") "AMK107BBJ476MA-RE")
        (field (name "MOUSER_PART_NUMBER") "963-AMK107BBJ476MARE")
        (field (name "RS_PART_NUMBER") "1843762P")
      )
      (libsource (lib "eagle-import") (part "AMK107BBJ476MA-RE"))
    )
    (comp (ref "C10")
      (value "100n")
      (footprint "eagle-import:CAPC1709X100N")
      (fields
        (field (name "MANUFACTURER_PART_NUMBER") "AMK107BBJ476MA-RE")
        (field (name "MOUSER_PART_NUMBER") "963-AMK107BBJ476MARE")
        (field (name "RS_PART_NUMBER") "1843762P")
      )
      (libsource (lib "eagle-import") (part "AMK107BBJ476MA-RE"))
    )
    (comp (ref "C11")
      (value "100n")
      (footprint "eagle-import:CAPC1709X100N")
      (fields
        (field (name "MANUFACTURER_PART_NUMBER") "AMK107BBJ476MA-RE")
        (field (name "MOUSER_PART_NUMBER") "963-AMK107BBJ476MARE")
        (field (name "RS_PART_NUMBER") "1843762P")
      )
      (libsource (lib "eagle-import") (part "AMK107BBJ476MA-RE"))
    )
    (comp (ref "C17")
      (value "4.7u")
      (footprint "eagle-import:CAPC1709X100N")
      (fields
        (field (name "MANUFACTURER_PART_NUMBER") "AMK107BBJ476MA-RE")
        (field (name "MOUSER_PART_NUMBER") "963-AMK107BBJ476MARE")
        (field (name "RS_PART_NUMBER") "1843762P")
      )
      (libsource (lib "eagle-import") (part "AMK107BBJ476MA-RE"))
    )
    (comp (ref "C18")
      (value "10n")
      (footprint "eagle-import:CAPC1709X100N")
      (fields
        (field (name "MANUFACTURER_PART_NUMBER") "AMK107BBJ476MA-RE")
        (field (name "MOUSER_PART_NUMBER") "963-AMK107BBJ476MARE")
        (field (name "RS_PART_NUMBER") "1843762P")
      )
      (libsource (lib "eagle-import") (part "AMK107BBJ476MA-RE"))
    )
    (comp (ref "C19")
      (value "1u")
      (footprint "eagle-import:CAPC1709X100N")
      (fields
        (field (name "MANUFACTURER_PART_NUMBER") "AMK107BBJ476MA-RE")
        (field (name "MOUSER_PART_NUMBER") "963-AMK107BBJ476MARE")
        (field (name "RS_PART_NUMBER") "1843762P")
      )
      (libsource (lib "eagle-import") (part "AMK107BBJ476MA-RE"))
    )
    (comp (ref "C22")
      (value "100n")
      (footprint "eagle-import:CAPC1608X90N")
      (fields
        (field (name "MANUFACTURER_PART_NUMBER") "GRM188B31A106KE69D")
        (field (name "RS_PART_NUMBER") "8847157P")
      )
      (libsource (lib "eagle-import") (part "GRM188B31A106KE69D"))
    )
    (comp (ref "C23")
      (value "0.1u")
      (footprint "eagle-import:CAPC1709X100N")
      (fields
        (field (name "MANUFACTURER_PART_NUMBER") "AMK107BBJ476MA-RE")
        (field (name "MOUSER_PART_NUMBER") "963-AMK107BBJ476MARE")
        (field (name "RS_PART_NUMBER") "1843762P")
      )
      (libsource (lib "eagle-import") (part "AMK107BBJ476MA-RE"))
    )
    (comp (ref "IC1")
      (value "STM32F302RBT6")
      (footprint "eagle-import:QFP50P1200X1200X160-64N")
      (fields (field (name "MOUSER_PART_NUMBER") "511-STM32F302RBT6"))
      (libsource (lib "eagle-import") (part "STM32F302RBT6"))
    )
    (comp (ref "IC2")
      (value "NCV7351D1ER2G")
      (footprint "eagle-import:SOIC127P600X175-8N")
      (fields (field (name "MOUSER_PART_NUMBER") "863-NCV7351D1ER2G"))
      (libsource (lib "eagle-import") (part "NCV7351D1ER2G"))
    )
    (comp (ref "J2")
      (value "USB-4AF203AS")
      (footprint "eagle-import:USB4AF203AS")
      (libsource (lib "eagle-import") (part "USB-4AF203AS"))
    )
    (comp (ref "JP1")
      (value "PINHD-1X3")
      (footprint "eagle-import:1X03")
      (libsource (lib "eagle-import") (part "PINHD-1X3"))
    )
    (comp (ref "JP2")
      (value "PINHD-1X3")
      (footprint "eagle-import:1X03")
      (libsource (lib "eagle-import") (part "PINHD-1X3"))
    )
    (comp (ref "JP3")
      (value "PINHD-1X3")
      (footprint "eagle-import:1X03")
      (libsource (lib "eagle-import") (part "PINHD-1X3"))
    )
    (comp (ref "LED2")
      (value "LED1608")
      (footprint "eagle-import:LED1608")
      (libsource (lib "eagle-import") (part "LED1608"))
    )
    (comp (ref "LED3")
      (value "LED1608")
      (footprint "eagle-import:LED1608")
      (libsource (lib "eagle-import") (part "LED1608"))
    )
    (comp (ref "LED14")
      (value "LED1608")
      (footprint "eagle-import:LED1608")
      (libsource (lib "eagle-import") (part "LED1608"))
    )
    (comp (ref "LED15")
      (value "LED1608")
      (footprint "eagle-import:LED1608")
      (libsource (lib "eagle-import") (part "LED1608"))
    )
    (comp (ref "LED16")
      (value "LED1608")
      (footprint "eagle-import:LED1608")
      (libsource (lib "eagle-import") (part "LED1608"))
    )
    (comp (ref "LED17")
      (value "LED1608")
      (footprint "eagle-import:LED1608")
      (libsource (lib "eagle-import") (part "LED1608"))
    )
    (comp (ref "LED29")
      (value "LED1608")
      (footprint "eagle-import:LED1608")
      (libsource (lib "eagle-import") (part "LED1608"))
    )
    (comp (ref "LED40")
      (value "LED1608")
      (footprint "eagle-import:LED1608")
      (libsource (lib "eagle-import") (part "LED1608"))
    )
    (comp (ref "LED41")
      (value "LED1608")
      (footprint "eagle-import:LED1608")
      (libsource (lib "eagle-import") (part "LED1608"))
    )
    (comp (ref "LED50")
      (value "LED1608")
      (footprint "eagle-import:LED1608")
      (libsource (lib "eagle-import") (part "LED1608"))
    )
    (comp (ref "LED51-G")
      (value "LED1608")
      (footprint "eagle-import:LED1608")
      (libsource (lib "eagle-import") (part "LED1608"))
    )
    (comp (ref "LED52-Y")
      (value "LED1608")
      (footprint "eagle-import:LED1608")
      (libsource (lib "eagle-import") (part "LED1608"))
    )
    (comp (ref "Q9")
      (value "SOT-23_NMOS")
      (footprint "eagle-import:SOT-23")
      (libsource (lib "eagle-import") (part "SOT-23_NMOS"))
    )
    (comp (ref "Q10")
      (value "SOT-23_NMOS")
      (footprint "eagle-import:SOT-23")
      (libsource (lib "eagle-import") (part "SOT-23_NMOS"))
    )
    (comp (ref "R1")
      (value "10k")
      (footprint "eagle-import:1608")
      (libsource (lib "eagle-import") (part "R1608"))
    )
    (comp (ref "R2")
      (value "1k")
      (footprint "eagle-import:R0603")
      (libsource (lib "eagle-import") (part "R-US_R0603"))
    )
    (comp (ref "R3")
      (value "1k")
      (footprint "eagle-import:R0603")
      (libsource (lib "eagle-import") (part "R-US_R0603"))
    )
    (comp (ref "R5")
      (value "120")
      (footprint "eagle-import:R0805")
      (libsource (lib "eagle-import") (part "R-EU_R0805"))
    )
    (comp (ref "R9")
      (value "10k")
      (footprint "eagle-import:SMD1608")
      (libsource (lib "eagle-import") (part "RESISTOR-US1608"))
    )
    (comp (ref "R10")
      (value "1k")
      (footprint "eagle-import:SMD1608")
      (libsource (lib "eagle-import") (part "RESISTOR-US1608"))
    )
    (comp (ref "R11")
      (value "10k")
      (footprint "eagle-import:SMD1608")
      (libsource (lib "eagle-import") (part "RESISTOR-US1608"))
    )
    (comp (ref "R20")
      (value "1k")
      (footprint "eagle-import:SMD1608")
      (libsource (lib "eagle-import") (part "RESISTOR-US1608"))
    )
    (comp (ref "R25")
      (value "10k")
      (footprint "eagle-import:R0603")
      (libsource (lib "eagle-import") (part "R-US_R0603"))
    )
    (comp (ref "R59")
      (value "10k")
      (footprint "eagle-import:SMD1608")
      (libsource (lib "eagle-import") (part "RESISTOR-US1608"))
    )
    (comp (ref "R60")
      (value "1k")
      (footprint "eagle-import:SMD1608")
      (libsource (lib "eagle-import") (part "RESISTOR-US1608"))
    )
    (comp (ref "R61")
      (value "10k")
      (footprint "eagle-import:SMD1608")
      (libsource (lib "eagle-import") (part "RESISTOR-US1608"))
    )
    (comp (ref "R62")
      (value "1k")
      (footprint "eagle-import:SMD1608")
      (libsource (lib "eagle-import") (part "RESISTOR-US1608"))
    )
    (comp (ref "R63")
      (value "10k")
      (footprint "eagle-import:SMD1608")
      (libsource (lib "eagle-import") (part "RESISTOR-US1608"))
    )
    (comp (ref "R64")
      (value "1k")
      (footprint "eagle-import:SMD1608")
      (libsource (lib "eagle-import") (part "RESISTOR-US1608"))
    )
    (comp (ref "R65")
      (value "10k")
      (footprint "eagle-import:SMD1608")
      (libsource (lib "eagle-import") (part "RESISTOR-US1608"))
    )
    (comp (ref "R66")
      (value "1k")
      (footprint "eagle-import:SMD1608")
      (libsource (lib "eagle-import") (part "RESISTOR-US1608"))
    )
    (comp (ref "R118")
      (value "1k")
      (footprint "eagle-import:R0603")
      (libsource (lib "eagle-import") (part "R-US_R0603"))
    )
    (comp (ref "R119")
      (value "1k")
      (footprint "eagle-import:SMD1608")
      (libsource (lib "eagle-import") (part "RESISTOR-US1608"))
    )
    (comp (ref "R120")
      (value "1k")
      (footprint "eagle-import:SMD1608")
      (libsource (lib "eagle-import") (part "RESISTOR-US1608"))
    )
    (comp (ref "R121")
      (value "10k")
      (footprint "eagle-import:SMD1608")
      (libsource (lib "eagle-import") (part "RESISTOR-US1608"))
    )
    (comp (ref "R122")
      (value "10k")
      (footprint "eagle-import:SMD1608")
      (libsource (lib "eagle-import") (part "RESISTOR-US1608"))
    )
    (comp (ref "S2")
      (value "TSHA-T-2.5B2-19E")
      (footprint "eagle-import:TSHAT25B219E")
      (libsource (lib "eagle-import") (part "TSHA-T-2.5B2-19E"))
    )
    (comp (ref "SL1")
      (value "MA06")
      (footprint "eagle-import:06PA")
      (libsource (lib "eagle-import") (part "MA06"))
    )
    (comp (ref "TR12")
      (value "2SC2712GR")
      (footprint "eagle-import:SOT-23")
      (libsource (lib "eagle-import") (part "SOT-23_NMOS"))
    )
    (comp (ref "TR13")
      (value "2SC2712GR")
      (footprint "eagle-import:SOT-23")
      (libsource (lib "eagle-import") (part "SOT-23_NMOS"))
    )
    (comp (ref "TR14")
      (value "2SC2712GR")
      (footprint "eagle-import:SOT-23")
      (libsource (lib "eagle-import") (part "SOT-23_NMOS"))
    )
    (comp (ref "TR17")
      (value "2SC2712GR")
      (footprint "eagle-import:SOT-23")
      (libsource (lib "eagle-import") (part "SOT-23_NMOS"))
    )
    (comp (ref "TR21")
      (value "2SC2712GR")
      (footprint "eagle-import:SOT-23")
      (libsource (lib "eagle-import") (part "SOT-23_NMOS"))
    )
    (comp (ref "TR22")
      (value "2SC2712GR")
      (footprint "eagle-import:SOT-23")
      (libsource (lib "eagle-import") (part "SOT-23_NMOS"))
    )
    (comp (ref "U1")
      (value "LD1117S33CTR")
      (footprint "eagle-import:SOT223")
      (fields (field (name "MF") "STMicroelectronics"))
      (libsource (lib "eagle-import") (part "LD1117S33CTR"))
    )
    (comp (ref "X8")
      (value "S4B-XH-A")
      (footprint "eagle-import:S4B-XH-A")
      (libsource (lib "eagle-import") (part "S4B-XH-A"))
    )
    (comp (ref "X18")
      (value "S2B-XH-A")
      (footprint "eagle-import:S2B-XH-A")
      (libsource (lib "eagle-import") (part "S2B-XH-A"))
    )
    (comp (ref "X19")
      (value "S2B-XH-A")
      (footprint "eagle-import:S2B-XH-A")
      (libsource (lib "eagle-import") (part "S2B-XH-A"))
    )
    (comp (ref "X22")
      (value "S3B-XH-A")
      (footprint "eagle-import:S3B-XH-A")
      (libsource (lib "eagle-import") (part "S3B-XH-A"))
    )
    (comp (ref "X25")
      (value "B2B-XH-A")
      (footprint "eagle-import:B2B-XH-A")
      (libsource (lib "eagle-import") (part "B2B-XH-A"))
    )
  )
  (nets
    (net (code "1") (name "3V3") (class "Default")
      (node (ref "C1") (pin "2") (pinfunction "2_2") (pintype "bidirectional"))
      (node (ref "C10") (pin "2") (pinfunction "2_2") (pintype "bidirectional"))
      (node (ref "C11") (pin "2") (pinfunction "2_2") (pintype "bidirectional"))
      (node (ref "C17") (pin "2") (pinfunction "2_2") (pintype "bidirectional"))
      (node (ref "C18") (pin "2") (pinfunction "2_2") (pintype "bidirectional"))
      (node (ref "C19") (pin "2") (pinfunction "2_2") (pintype "bidirectional"))
      (node (ref "C2") (pin "2") (pinfunction "2_2") (pintype "bidirectional"))
      (node (ref "C9") (pin "2") (pinfunction "2_2") (pintype "bidirectional"))
      (node (ref "IC1") (pin "1") (pinfunction "VBAT_1") (pintype "bidirectional"))
      (node (ref "IC1") (pin "13") (pinfunction "VDDA_13") (pintype "bidirectional"))
      (node (ref "IC1") (pin "19") (pinfunction "VDD_1_19") (pintype "bidirectional"))
      (node (ref "IC1") (pin "32") (pinfunction "VDD_2_32") (pintype "bidirectional"))
      (node (ref "IC1") (pin "48") (pinfunction "VDD_3_48") (pintype "bidirectional"))
      (node (ref "IC1") (pin "64") (pinfunction "VDD_4_64") (pintype "bidirectional"))
      (node (ref "IC4") (pin "1") (pinfunction "ANODE_1_1") (pintype "bidirectional"))
      (node (ref "IC4") (pin "3") (pinfunction "ANODE_2_3") (pintype "bidirectional"))
      (node (ref "IC4") (pin "5") (pinfunction "ANODE_3_5") (pintype "bidirectional"))
      (node (ref "IC4") (pin "7") (pinfunction "ANODE_4_7") (pintype "bidirectional"))
      (node (ref "IC5") (pin "1") (pinfunction "ANODE_1_1") (pintype "bidirectional"))
      (node (ref "IC5") (pin "3") (pinfunction "ANODE_2_3") (pintype "bidirectional"))
      (node (ref "IC5") (pin "5") (pinfunction "ANODE_3_5") (pintype "bidirectional"))
      (node (ref "IC5") (pin "7") (pinfunction "ANODE_4_7") (pintype "bidirectional"))
      (node (ref "IC7") (pin "1") (pinfunction "ANODE_1_1") (pintype "bidirectional"))
      (node (ref "IC7") (pin "3") (pinfunction "ANODE_2_3") (pintype "bidirectional"))
      (node (ref "IC7") (pin "5") (pinfunction "ANODE_3_5") (pintype "bidirectional"))
      (node (ref "IC7") (pin "7") (pinfunction "ANODE_4_7") (pintype "bidirectional"))
      (node (ref "IC8") (pin "1") (pinfunction "ANODE_1_1") (pintype "bidirectional"))
      (node (ref "IC8") (pin "3") (pinfunction "ANODE_2_3") (pintype "bidirectional"))
      (node (ref "IC8") (pin "5") (pinfunction "ANODE_3_5") (pintype "bidirectional"))
      (node (ref "IC8") (pin "7") (pinfunction "ANODE_4_7") (pintype "bidirectional"))
      (node (ref "IC9") (pin "1") (pinfunction "ANODE_1_1") (pintype "bidirectional"))
      (node (ref "IC9") (pin "3") (pinfunction "ANODE_2_3") (pintype "bidirectional"))
      (node (ref "IC9") (pin "5") (pinfunction "ANODE_3_5") (pintype "bidirectional"))
      (node (ref "IC9") (pin "7") (pinfunction "ANODE_4_7") (pintype "bidirectional"))
      (node (ref "LED3") (pin "A") (pinfunction "A_A") (pintype "passive"))
      (node (ref "R106") (pin "1") (pinfunction "1_1") (pintype "passive"))
      (node (ref "R108") (pin "1") (pinfunction "1_1") (pintype "passive"))
      (node (ref "R110") (pin "1") (pinfunction "1_1") (pintype "passive"))
      (node (ref "R112") (pin "1") (pinfunction "1_1") (pintype "passive"))
      (node (ref "R45") (pin "1") (pinfunction "1_1") (pintype "passive"))
      (node (ref "R55") (pin "1") (pinfunction "1_1") (pintype "passive"))
      (node (ref "R57") (pin "1") (pinfunction "1_1") (pintype "passive"))
      (node (ref "R67") (pin "1") (pinfunction "1_1") (pintype "passive"))
      (node (ref "R69") (pin "1") (pinfunction "1_1") (pintype "passive"))
      (node (ref "R71") (pin "1") (pinfunction "1_1") (pintype "passive"))
      (node (ref "R73") (pin "1") (pinfunction "1_1") (pintype "passive"))
      (node (ref "R75") (pin "1") (pinfunction "1_1") (pintype "passive"))
      (node (ref "R77") (pin "1") (pinfunction "1_1") (pintype "passive"))
      (node (ref "R87") (pin "1") (pinfunction "1_1") (pintype "passive"))
      (node (ref "R89") (pin "1") (pinfunction "1_1") (pintype "passive"))
      (node (ref "R91") (pin "1") (pinfunction "1_1") (pintype "passive"))
      (node (ref "R93") (pin "1") (pinfunction "1_1") (pintype "passive"))
      (node (ref "R95") (pin "1") (pinfunction "1_1") (pintype "passive"))
      (node (ref "R97") (pin "1") (pinfunction "1_1") (pintype "passive"))
      (node (ref "R99") (pin "1") (pinfunction "1_1") (pintype "passive"))
      (node (ref "SL1") (pin "1") (pinfunction "1_1") (pintype "passive"))
      (node (ref "U1") (pin "2") (pinfunction "OUT_2") (pintype "output"))
      (node (ref "U1") (pin "4") (pinfunction "OUT_4") (pintype "output"))
      (node (ref "X22") (pin "2") (pinfunction "2_2") (pintype "passive"))
    )
    (net (code "2") (name "5V") (class "Default")
      (node (ref "C22") (pin "2") (pinfunction "2_2") (pintype "bidirectional"))
      (node (ref "IC2") (pin "3") (pinfunction "VCC_3") (pintype "bidirectional"))
      (node (ref "IC2") (pin "5") (pinfunction "EN_5") (pintype "bidirectional"))
      (node (ref "J2") (pin "1") (pinfunction "1_1") (pintype "bidirectional"))
      (node (ref "J2") (pin "5") (pinfunction "5_5") (pintype "bidirectional"))
      (node (ref "LED51-G") (pin "A") (pinfunction "A_A") (pintype "passive"))
      (node (ref "LED52-Y") (pin "A") (pinfunction "A_A") (pintype "passive"))
      (node (ref "R10") (pin "1") (pinfunction "1_1") (pintype "passive"))
      (node (ref "R2") (pin "1") (pinfunction "1_1") (pintype "passive"))
      (node (ref "R20") (pin "1") (pinfunction "1_1") (pintype "passive"))
      (node (ref "R60") (pin "1") (pinfunction "1_1") (pintype "passive"))
      (node (ref "R62") (pin "1") (pinfunction "1_1") (pintype "passive"))
      (node (ref "R64") (pin "1") (pinfunction "1_1") (pintype "passive"))
      (node (ref "R66") (pin "1") (pinfunction "1_1") (pintype "passive"))
      (node (ref "U1") (pin "3") (pinfunction "IN_3") (pintype "input"))
      (node (ref "X22") (pin "1") (pinfunction "1_1") (pintype "passive"))
    )
    (net (code "3") (name "12V") (class "Default")
      (node (ref "C5") (pin "1") (pinfunction "+_1") (pintype "bidirectional"))
      (node (ref "IC6") (pin "10") (pinfunction "COMMON_10") (pintype "bidirectional"))
      (node (ref "IC7") (pin "10") (pinfunction "COLLECTOR_1_10") (pintype "bidirectional"))
      (node (ref "IC7") (pin "12") (pinfunction "COLLECTOR_2_12") (pintype "bidirectional"))
      (node (ref "IC7") (pin "14") (pinfunction "COLLECTOR_3_14") (pintype "bidirectional"))
      (node (ref "IC7") (pin "16") (pinfunction "COLLECTOR_4_16") (pintype "bidirectional"))
      (node (ref "IC8") (pin "10") (pinfunction "COLLECTOR_1_10") (pintype "bidirectional"))
      (node (ref "IC8") (pin "12") (pinfunction "COLLECTOR_2_12") (pintype "bidirectional"))
      (node (ref "IC8") (pin "14") (pinfunction "COLLECTOR_3_14") (pintype "bidirectional"))
      (node (ref "IC8") (pin "16") (pinfunction "COLLECTOR_4_16") (pintype "bidirectional"))
      (node (ref "LED41") (pin "A") (pinfunction "A_A") (pintype "passive"))
      (node (ref "X1") (pin "1") (pinfunction "1_1") (pintype "passive"))
      (node (ref "X10") (pin "1") (pinfunction "1_1") (pintype "passive"))
      (node (ref "X11") (pin "1") (pinfunction "1_1") (pintype "passive"))
      (node (ref "X12") (pin "1") (pinfunction "1_1") (pintype "passive"))
      (node (ref "X25") (pin "1") (pinfunction "1_1") (pintype "passive"))
      (node (ref "X5") (pin "1") (pinfunction "1_1") (pintype "passive"))
      (node (ref "X6") (pin "1") (pinfunction "1_1") (pintype "passive"))
      (node (ref "X7") (pin "1") (pinfunction "1_1") (pintype "passive"))
      (node (ref "X9") (pin "1") (pinfunction "1_1") (pintype "passive"))
    )
    (net (code "4") (name "CANH") (class "Default")
      (node (ref "IC2") (pin "7") (pinfunction "CANH_7") (pintype "bidirectional"))
      (node (ref "J2") (pin "2") (pinfunction "2_2") (pintype "bidirectional"))
      (node (ref "J2") (pin "6") (pinfunction "6_6") (pintype "bidirectional"))
      (node (ref "R5") (pin "2") (pinfunction "2_2") (pintype "passive"))
    )
    (net (code "5") (name "CANL") (class "Default")
      (node (ref "IC2") (pin "6") (pinfunction "CANL_6") (pintype "bidirectional"))
      (node (ref "J2") (pin "3") (pinfunction "3_3") (pintype "bidirectional"))
      (node (ref "J2") (pin "7") (pinfunction "7_7") (pintype "bidirectional"))
      (node (ref "R5") (pin "1") (pinfunction "1_1") (pintype "passive"))
    )
    (net (code "6") (name "CAN_RX") (class "Default")
      (node (ref "IC1") (pin "44") (pinfunction "PA11_44") (pintype "bidirectional"))
      (node (ref "IC2") (pin "4") (pinfunction "RXD_4") (pintype "bidirectional"))
      (node (ref "R122") (pin "2") (pinfunction "2_2") (pintype "passive"))
    )
    (net (code "7") (name "CAN_TX") (class "Default")
      (node (ref "IC1") (pin "45") (pinfunction "PA12_45") (pintype "bidirectional"))
      (node (ref "IC2") (pin "1") (pinfunction "TXD_1") (pintype "bidirectional"))
      (node (ref "R121") (pin "2") (pinfunction "2_2") (pintype "passive"))
    )
    (net (code "8") (name "CATHODE-SE_1") (class "Default")
      (node (ref "LED35") (pin "K") (pinfunction "K_K") (pintype "passive"))
      (node (ref "R29") (pin "2") (pinfunction "2_2") (pintype "passive"))
      (node (ref "TR2") (pin "3") (pinfunction "D_3") (pintype "bidirectional"))
    )
    (net (code "9") (name "CATHODE-SE_2") (class "Default")
      (node (ref "LED37") (pin "K") (pinfunction "K_K") (pintype "passive"))
      (node (ref "R30") (pin "2") (pinfunction "2_2") (pintype "passive"))
      (node (ref "TR4") (pin "3") (pinfunction "D_3") (pintype "bidirectional"))
    )
    (net (code "10") (name "CATHODE-SE_3") (class "Default")
      (node (ref "LED44") (pin "K") (pinfunction "K_K") (pintype "passive"))
      (node (ref "R31") (pin "2") (pinfunction "2_2") (pintype "passive"))
      (node (ref "TR23") (pin "3") (pinfunction "D_3") (pintype "bidirectional"))
    )
    (net (code "11") (name "CATHODE-SE_4") (class "Default")
      (node (ref "LED7") (pin "K") (pinfunction "K_K") (pintype "passive"))
      (node (ref "R32") (pin "2") (pinfunction "2_2") (pintype "passive"))
      (node (ref "TR16") (pin "3") (pinfunction "D_3") (pintype "bidirectional"))
    )
    (net (code "12") (name "CATHODE-SE_5") (class "Default")
      (node (ref "LED33") (pin "K") (pinfunction "K_K") (pintype "passive"))
      (node (ref "R37") (pin "2") (pinfunction "2_2") (pintype "passive"))
      (node (ref "TR19") (pin "3") (pinfunction "D_3") (pintype "bidirectional"))
    )
    (net (code "13") (name "CATHODE-SE_6") (class "Default")
      (node (ref "LED42") (pin "K") (pinfunction "K_K") (pintype "passive"))
      (node (ref "R38") (pin "2") (pinfunction "2_2") (pintype "passive"))
      (node (ref "TR25") (pin "3") (pinfunction "D_3") (pintype "bidirectional"))
    )
    (net (code "14") (name "CATHODE-SE_7") (class "Default")
      (node (ref "LED36") (pin "K") (pinfunction "K_K") (pintype "passive"))
      (node (ref "R39") (pin "2") (pinfunction "2_2") (pintype "passive"))
      (node (ref "TR3") (pin "3") (pinfunction "D_3") (pintype "bidirectional"))
    )
    (net (code "15") (name "CATHODE-SE_8") (class "Default")
      (node (ref "LED38") (pin "K") (pinfunction "K_K") (pintype "passive"))
      (node (ref "R40") (pin "2") (pinfunction "2_2") (pintype "passive"))
      (node (ref "TR15") (pin "3") (pinfunction "D_3") (pintype "bidirectional"))
    )
    (net (code "16") (name "CATHODE-SE_9") (class "Default")
      (node (ref "LED45") (pin "K") (pinfunction "K_K") (pintype "passive"))
      (node (ref "R26") (pin "2") (pinfunction "2_2") (pintype "passive"))
      (node (ref "TR24") (pin "3") (pinfunction "D_3") (pintype "bidirectional"))
    )
    (net (code "17") (name "CATHODE-SE_10") (class "Default")
      (node (ref "LED32") (pin "K") (pinfunction "K_K") (pintype "passive"))
      (node (ref "R27") (pin "2") (pinfunction "2_2") (pintype "passive"))
      (node (ref "TR18") (pin "3") (pinfunction "D_3") (pintype "bidirectional"))
    )
    (net (code "18") (name "CATHODE-SE_11") (class "Default")
      (node (ref "LED34") (pin "K") (pinfunction "K_K") (pintype "passive"))
      (node (ref "R28") (pin "2") (pinfunction "2_2") (pintype "passive"))
      (node (ref "TR20") (pin "3") (pinfunction "D_3") (pintype "bidirectional"))
    )
    (net (code "19") (name "CATHODE-SE_12") (class "Default")
      (node (ref "LED43") (pin "K") (pinfunction "K_K") (pintype "passive"))
      (node (ref "R101") (pin "2") (pinfunction "2_2") (pintype "passive"))
      (node (ref "TR26") (pin "3") (pinfunction "D_3") (pintype "bidirectional"))
    )
    (net (code "20") (name "CATHODE-SO_1") (class "Default")
      (node (ref "LED24") (pin "K") (pinfunction "K_K") (pintype "passive"))
      (node (ref "R4") (pin "2") (pinfunction "2_2") (pintype "passive"))
      (node (ref "TR9") (pin "3") (pinfunction "D_3") (pintype "bidirectional"))
    )
    (net (code "21") (name "CATHODE-SO_2") (class "Default")
      (node (ref "LED25") (pin "K") (pinfunction "K_K") (pintype "passive"))
      (node (ref "R6") (pin "2") (pinfunction "2_2") (pintype "passive"))
      (node (ref "TR10") (pin "3") (pinfunction "D_3") (pintype "bidirectional"))
    )
    (net (code "22") (name "CATHODE-SO_3") (class "Default")
      (node (ref "LED26") (pin "K") (pinfunction "K_K") (pintype "passive"))
      (node (ref "R7") (pin "2") (pinfunction "2_2") (pintype "passive"))
      (node (ref "TR11") (pin "3") (pinfunction "D_3") (pintype "bidirectional"))
    )
    (net (code "23") (name "CATHODE-SO_4") (class "Default")
      (node (ref "LED27") (pin "K") (pinfunction "K_K") (pintype "passive"))
      (node (ref "R8") (pin "2") (pinfunction "2_2") (pintype "passive"))
      (node (ref "TR1") (pin "3") (pinfunction "D_3") (pintype "bidirectional"))
    )
    (net (code "24") (name "CATHODE-SO_5") (class "Default")
      (node (ref "LED39") (pin "K") (pinfunction "K_K") (pintype "passive"))
      (node (ref "R21") (pin "2") (pinfunction "2_2") (pintype "passive"))
      (node (ref "TR5") (pin "3") (pinfunction "D_3") (pintype "bidirectional"))
    )
    (net (code "25") (name "CATHODE-SO_6") (class "Default")
      (node (ref "LED21") (pin "K") (pinfunction "K_K") (pintype "passive"))
      (node (ref "R22") (pin "2") (pinfunction "2_2") (pintype "passive"))
      (node (ref "TR6") (pin "3") (pinfunction "D_3") (pintype "bidirectional"))
    )
    (net (code "26") (name "CATHODE-SO_7") (class "Default")
      (node (ref "LED22") (pin "K") (pinfunction "K_K") (pintype "passive"))
      (node (ref "R23") (pin "2") (pinfunction "2_2") (pintype "passive"))
      (node (ref "TR7") (pin "3") (pinfunction "D_3") (pintype "bidirectional"))
    )
    (net (code "27") (name "CATHODE-SO_8") (class "Default")
      (node (ref "LED23") (pin "K") (pinfunction "K_K") (pintype "passive"))
      (node (ref "R24") (pin "2") (pinfunction "2_2") (pintype "passive"))
      (node (ref "TR8") (pin "3") (pinfunction "D_3") (pintype "bidirectional"))
    )
    (net (code "28") (name "DCDC_OUT") (class "Default")
      (node (ref "IC4") (pin "10") (pinfunction "COLLECTOR_1_10") (pintype "bidirectional"))
      (node (ref "IC4") (pin "12") (pinfunction "COLLECTOR_2_12") (pintype "bidirectional"))
      (node (ref "IC4") (pin "14") (pinfunction "COLLECTOR_3_14") (pintype "bidirectional"))
      (node (ref "IC4") (pin "16") (pinfunction "COLLECTOR_4_16") (pintype "bidirectional"))
      (node (ref "IC5") (pin "10") (pinfunction "COLLECTOR_1_10") (pintype "bidirectional"))
      (node (ref "IC5") (pin "12") (pinfunction "COLLECTOR_2_12") (pintype "bidirectional"))
      (node (ref "IC5") (pin "14") (pinfunction "COLLECTOR_3_14") (pintype "bidirectional"))
      (node (ref "IC5") (pin "16") (pinfunction "COLLECTOR_4_16") (pintype "bidirectional"))
      (node (ref "IC9") (pin "10") (pinfunction "COLLECTOR_1_10") (pintype "bidirectional"))
      (node (ref "IC9") (pin "12") (pinfunction "COLLECTOR_2_12") (pintype "bidirectional"))
      (node (ref "IC9") (pin "14") (pinfunction "COLLECTOR_3_14") (pintype "bidirectional"))
      (node (ref "IC9") (pin "16") (pinfunction "COLLECTOR_4_16") (pintype "bidirectional"))
      (node (ref "R118") (pin "1") (pinfunction "1_1") (pintype "passive"))
      (node (ref "X13") (pin "1") (pinfunction "1_1") (pintype "passive"))
      (node (ref "X14") (pin "1") (pinfunction "1_1") (pintype "passive"))
      (node (ref "X15") (pin "1") (pinfunction "1_1") (pintype "passive"))
      (node (ref "X16") (pin "1") (pinfunction "1_1") (pintype "passive"))
      (node (ref "X17") (pin "1") (pinfunction "1_1") (pintype "passive"))
      (node (ref "X2") (pin "1") (pinfunction "1_1") (pintype "passive"))
      (node (ref "X20") (pin "1") (pinfunction "1_1") (pintype "passive"))
      (node (ref "X21") (pin "1") (pinfunction "1_1") (pintype "passive"))
      (node (ref "X23") (pin "1") (pinfunction "1_1") (pintype "passive"))
      (node (ref "X24") (pin "1") (pinfunction "1_1") (pintype "passive"))
      (node (ref "X3") (pin "1") (pinfunction "1_1") (pintype "passive"))
      (node (ref "X4") (pin "1") (pinfunction "1_1") (pintype "passive"))
    )
    (net (code "29") (name "GND") (class "Default")
      (node (ref "C1") (pin "1") (pinfunction "1_1") (pintype "bidirectional"))
      (node (ref "C10") (pin "1") (pinfunction "1_1") (pintype "bidirectional"))
      (node (ref "C11") (pin "1") (pinfunction "1_1") (pintype "bidirectional"))
      (node (ref "C17") (pin "1") (pinfunction "1_1") (pintype "bidirectional"))
      (node (ref "C18") (pin "1") (pinfunction "1_1") (pintype "bidirectional"))
      (node (ref "C19") (pin "1") (pinfunction "1_1") (pintype "bidirectional"))
      (node (ref "C2") (pin "1") (pinfunction "1_1") (pintype "bidirectional"))
      (node (ref "C22") (pin "1") (pinfunction "1_1") (pintype "bidirectional"))
      (node (ref "C23") (pin "1") (pinfunction "1_1") (pintype "bidirectional"))
      (node (ref "C9") (pin "1") (pinfunction "1_1") (pintype "bidirectional"))
      (node (ref "IC1") (pin "12") (pinfunction "VSSA/VREF-_12") (pintype "bidirectional"))
      (node (ref "IC1") (pin "31") (pinfunction "VSS_1_31") (pintype "bidirectional"))
      (node (ref "IC1") (pin "47") (pinfunction "VSS_2_47") (pintype "bidirectional"))
      (node (ref "IC1") (pin "63") (pinfunction "VSS_3_63") (pintype "bidirectional"))
      (node (ref "IC2") (pin "2") (pinfunction "GND_2") (pintype "bidirectional"))
      (node (ref "IC2") (pin "8") (pinfunction "S_8") (pintype "bidirectional"))
      (node (ref "J2") (pin "4") (pinfunction "4_4") (pintype "bidirectional"))
      (node (ref "J2") (pin "8") (pinfunction "8_8") (pintype "bidirectional"))
      (node (ref "LED2") (pin "K") (pinfunction "K_K") (pintype "passive"))
      (node (ref "Q10") (pin "2") (pinfunction "S_2") (pintype "bidirectional"))
      (node (ref "Q9") (pin "2") (pinfunction "S_2") (pintype "bidirectional"))
      (node (ref "R1") (pin "2") (pinfunction "2_2") (pintype "passive"))
      (node (ref "R3") (pin "2") (pinfunction "2_2") (pintype "passive"))
      (node (ref "S2") (pin "C1") (pinfunction "COM_1_C1") (pintype "bidirectional"))
      (node (ref "S2") (pin "D1") (pinfunction "COM_2_D1") (pintype "bidirectional"))
      (node (ref "SL1") (pin "3") (pinfunction "3_3") (pintype "passive"))
      (node (ref "TR1") (pin "2") (pinfunction "S_2") (pintype "bidirectional"))
      (node (ref "TR10") (pin "2") (pinfunction "S_2") (pintype "bidirectional"))
      (node (ref "TR11") (pin "2") (pinfunction "S_2") (pintype "bidirectional"))
      (node (ref "TR12") (pin "2") (pinfunction "S_2") (pintype "bidirectional"))
      (node (ref "TR13") (pin "2") (pinfunction "S_2") (pintype "bidirectional"))
      (node (ref "TR14") (pin "2") (pinfunction "S_2") (pintype "bidirectional"))
      (node (ref "TR15") (pin "2") (pinfunction "S_2") (pintype "bidirectional"))
      (node (ref "TR16") (pin "2") (pinfunction "S_2") (pintype "bidirectional"))
      (node (ref "TR17") (pin "2") (pinfunction "S_2") (pintype "bidirectional"))
      (node (ref "TR18") (pin "2") (pinfunction "S_2") (pintype "bidirectional"))
      (node (ref "TR19") (pin "2") (pinfunction "S_2") (pintype "bidirectional"))
      (node (ref "TR2") (pin "2") (pinfunction "S_2") (pintype "bidirectional"))
      (node (ref "TR20") (pin "2") (pinfunction "S_2") (pintype "bidirectional"))
      (node (ref "TR21") (pin "2") (pinfunction "S_2") (pintype "bidirectional"))
      (node (ref "TR22") (pin "2") (pinfunction "S_2") (pintype "bidirectional"))
      (node (ref "TR23") (pin "2") (pinfunction "S_2") (pintype "bidirectional"))
      (node (ref "TR24") (pin "2") (pinfunction "S_2") (pintype "bidirectional"))
      (node (ref "TR25") (pin "2") (pinfunction "S_2") (pintype "bidirectional"))
      (node (ref "TR26") (pin "2") (pinfunction "S_2") (pintype "bidirectional"))
      (node (ref "TR3") (pin "2") (pinfunction "S_2") (pintype "bidirectional"))
      (node (ref "TR4") (pin "2") (pinfunction "S_2") (pintype "bidirectional"))
      (node (ref "TR5") (pin "2") (pinfunction "S_2") (pintype "bidirectional"))
      (node (ref "TR6") (pin "2") (pinfunction "S_2") (pintype "bidirectional"))
      (node (ref "TR7") (pin "2") (pinfunction "S_2") (pintype "bidirectional"))
      (node (ref "TR8") (pin "2") (pinfunction "S_2") (pintype "bidirectional"))
      (node (ref "TR9") (pin "2") (pinfunction "S_2") (pintype "bidirectional"))
      (node (ref "U1") (pin "1") (pinfunction "GND_1") (pintype "passive"))
      (node (ref "X22") (pin "3") (pinfunction "3_3") (pintype "passive"))
    )
    (net (code "30") (name "GND-M") (class "Default")
      (node (ref "C5") (pin "2") (pinfunction "-_2") (pintype "bidirectional"))
      (node (ref "IC6") (pin "9") (pinfunction "GND_9") (pintype "bidirectional"))
      (node (ref "LED50") (pin "K") (pinfunction "K_K") (pintype "passive"))
      (node (ref "R102") (pin "1") (pinfunction "1_1") (pintype "passive"))
      (node (ref "R103") (pin "1") (pinfunction "1_1") (pintype "passive"))
      (node (ref "R104") (pin "1") (pinfunction "1_1") (pintype "passive"))
      (node (ref "R105") (pin "1") (pinfunction "1_1") (pintype "passive"))
      (node (ref "R114") (pin "2") (pinfunction "2_2") (pintype "passive"))
      (node (ref "R115") (pin "2") (pinfunction "2_2") (pintype "passive"))
      (node (ref "R116") (pin "2") (pinfunction "2_2") (pintype "passive"))
      (node (ref "R117") (pin "2") (pinfunction "2_2") (pintype "passive"))
      (node (ref "R12") (pin "1") (pinfunction "1_1") (pintype "passive"))
      (node (ref "R13") (pin "1") (pinfunction "1_1") (pintype "passive"))
      (node (ref "R14") (pin "1") (pinfunction "1_1") (pintype "passive"))
      (node (ref "R15") (pin "1") (pinfunction "1_1") (pintype "passive"))
      (node (ref "R16") (pin "1") (pinfunction "1_1") (pintype "passive"))
      (node (ref "R17") (pin "1") (pinfunction "1_1") (pintype "passive"))
      (node (ref "R18") (pin "1") (pinfunction "1_1") (pintype "passive"))
      (node (ref "R19") (pin "1") (pinfunction "1_1") (pintype "passive"))
      (node (ref "R25") (pin "2") (pinfunction "2_2") (pintype "passive"))
      (node (ref "R33") (pin "1") (pinfunction "1_1") (pintype "passive"))
      (node (ref "R34") (pin "1") (pinfunction "1_1") (pintype "passive"))
      (node (ref "R35") (pin "1") (pinfunction "1_1") (pintype "passive"))
      (node (ref "R36") (pin "1") (pinfunction "1_1") (pintype "passive"))
      (node (ref "R41") (pin "1") (pinfunction "1_1") (pintype "passive"))
      (node (ref "R42") (pin "1") (pinfunction "1_1") (pintype "passive"))
      (node (ref "R43") (pin "1") (pinfunction "1_1") (pintype "passive"))
      (node (ref "R44") (pin "1") (pinfunction "1_1") (pintype "passive"))
      (node (ref "R46") (pin "2") (pinfunction "2_2") (pintype "passive"))
      (node (ref "R47") (pin "2") (pinfunction "2_2") (pintype "passive"))
      (node (ref "R48") (pin "2") (pinfunction "2_2") (pintype "passive"))
      (node (ref "R49") (pin "2") (pinfunction "2_2") (pintype "passive"))
      (node (ref "R50") (pin "2") (pinfunction "2_2") (pintype "passive"))
      (node (ref "R51") (pin "2") (pinfunction "2_2") (pintype "passive"))
      (node (ref "R52") (pin "2") (pinfunction "2_2") (pintype "passive"))
      (node (ref "R53") (pin "2") (pinfunction "2_2") (pintype "passive"))
      (node (ref "R78") (pin "2") (pinfunction "2_2") (pintype "passive"))
      (node (ref "R79") (pin "2") (pinfunction "2_2") (pintype "passive"))
      (node (ref "R80") (pin "2") (pinfunction "2_2") (pintype "passive"))
      (node (ref "R81") (pin "2") (pinfunction "2_2") (pintype "passive"))
      (node (ref "R82") (pin "2") (pinfunction "2_2") (pintype "passive"))
      (node (ref "R83") (pin "2") (pinfunction "2_2") (pintype "passive"))
      (node (ref "R84") (pin "2") (pinfunction "2_2") (pintype "passive"))
      (node (ref "R85") (pin "2") (pinfunction "2_2") (pintype "passive"))
      (node (ref "X13") (pin "3") (pinfunction "3_3") (pintype "passive"))
      (node (ref "X14") (pin "3") (pinfunction "3_3") (pintype "passive"))
      (node (ref "X15") (pin "3") (pinfunction "3_3") (pintype "passive"))
      (node (ref "X16") (pin "3") (pinfunction "3_3") (pintype "passive"))
      (node (ref "X17") (pin "3") (pinfunction "3_3") (pintype "passive"))
      (node (ref "X2") (pin "3") (pinfunction "3_3") (pintype "passive"))
      (node (ref "X20") (pin "3") (pinfunction "3_3") (pintype "passive"))
      (node (ref "X21") (pin "3") (pinfunction "3_3") (pintype "passive"))
      (node (ref "X23") (pin "3") (pinfunction "3_3") (pintype "passive"))
      (node (ref "X24") (pin "3") (pinfunction "3_3") (pintype "passive"))
      (node (ref "X25") (pin "2") (pinfunction "2_2") (pintype "passive"))
      (node (ref "X3") (pin "3") (pinfunction "3_3") (pintype "passive"))
      (node (ref "X4") (pin "3") (pinfunction "3_3") (pintype "passive"))
    )
    (net (code "31") (name "NRST") (class "Default")
      (node (ref "C23") (pin "2") (pinfunction "2_2") (pintype "bidirectional"))
      (node (ref "IC1") (pin "7") (pinfunction "NRST_7") (pintype "bidirectional"))
      (node (ref "S2") (pin "A1") (pinfunction "NO_1_A1") (pintype "bidirectional"))
      (node (ref "SL1") (pin "5") (pinfunction "5_5") (pintype "passive"))
    )
    (net (code "32") (name "Net-(IC1-BOOT0)") (class "Default")
      (node (ref "IC1") (pin "60") (pinfunction "BOOT0_60") (pintype "bidirectional"))
      (node (ref "R1") (pin "1") (pinfunction "1_1") (pintype "passive"))
    )
    (net (code "33") (name "Net-(IC4-CATHODE_1)") (class "Default")
      (node (ref "IC4") (pin "2") (pinfunction "CATHODE_1_2") (pintype "bidirectional"))
      (node (ref "R37") (pin "1") (pinfunction "1_1") (pintype "passive"))
    )
    (net (code "34") (name "Net-(IC4-CATHODE_2)") (class "Default")
      (node (ref "IC4") (pin "4") (pinfunction "CATHODE_2_4") (pintype "bidirectional"))
      (node (ref "R38") (pin "1") (pinfunction "1_1") (pintype "passive"))
    )
    (net (code "35") (name "Net-(IC4-CATHODE_3)") (class "Default")
      (node (ref "IC4") (pin "6") (pinfunction "CATHODE_3_6") (pintype "bidirectional"))
      (node (ref "R39") (pin "1") (pinfunction "1_1") (pintype "passive"))
    )
    (net (code "36") (name "Net-(IC4-CATHODE_4)") (class "Default")
      (node (ref "IC4") (pin "8") (pinfunction "CATHODE_4_8") (pintype "bidirectional"))
      (node (ref "R40") (pin "1") (pinfunction "1_1") (pintype "passive"))
    )
    (net (code "37") (name "Net-(IC5-CATHODE_1)") (class "Default")
      (node (ref "IC5") (pin "2") (pinfunction "CATHODE_1_2") (pintype "bidirectional"))
      (node (ref "R26") (pin "1") (pinfunction "1_1") (pintype "passive"))
    )
    (net (code "38") (name "Net-(IC5-CATHODE_2)") (class "Default")
      (node (ref "IC5") (pin "4") (pinfunction "CATHODE_2_4") (pintype "bidirectional"))
      (node (ref "R27") (pin "1") (pinfunction "1_1") (pintype "passive"))
    )
    (net (code "39") (name "Net-(IC5-CATHODE_3)") (class "Default")
      (node (ref "IC5") (pin "6") (pinfunction "CATHODE_3_6") (pintype "bidirectional"))
      (node (ref "R28") (pin "1") (pinfunction "1_1") (pintype "passive"))
    )
    (net (code "40") (name "Net-(IC5-CATHODE_4)") (class "Default")
      (node (ref "IC5") (pin "8") (pinfunction "CATHODE_4_8") (pintype "bidirectional"))
      (node (ref "R101") (pin "1") (pinfunction "1_1") (pintype "passive"))
    )
    (net (code "41") (name "Net-(IC7-CATHODE_1)") (class "Default")
      (node (ref "IC7") (pin "2") (pinfunction "CATHODE_1_2") (pintype "bidirectional"))
      (node (ref "R4") (pin "1") (pinfunction "1_1") (pintype "passive"))
    )
    (net (code "42") (name "Net-(IC7-CATHODE_2)") (class "Default")
      (node (ref "IC7") (pin "4") (pinfunction "CATHODE_2_4") (pintype "bidirectional"))
      (node (ref "R6") (pin "1") (pinfunction "1_1") (pintype "passive"))
    )
    (net (code "43") (name "Net-(IC7-CATHODE_3)") (class "Default")
      (node (ref "IC7") (pin "6") (pinfunction "CATHODE_3_6") (pintype "bidirectional"))
      (node (ref "R7") (pin "1") (pinfunction "1_1") (pintype "passive"))
    )
    (net (code "44") (name "Net-(IC7-CATHODE_4)") (class "Default")
      (node (ref "IC7") (pin "8") (pinfunction "CATHODE_4_8") (pintype "bidirectional"))
      (node (ref "R8") (pin "1") (pinfunction "1_1") (pintype "passive"))
    )
    (net (code "45") (name "Net-(IC8-CATHODE_1)") (class "Default")
      (node (ref "IC8") (pin "2") (pinfunction "CATHODE_1_2") (pintype "bidirectional"))
      (node (ref "R21") (pin "1") (pinfunction "1_1") (pintype "passive"))
    )
    (net (code "46") (name "Net-(IC8-CATHODE_2)") (class "Default")
      (node (ref "IC8") (pin "4") (pinfunction "CATHODE_2_4") (pintype "bidirectional"))
      (node (ref "R22") (pin "1") (pinfunction "1_1") (pintype "passive"))
    )
    (net (code "47") (name "Net-(IC8-CATHODE_3)") (class "Default")
      (node (ref "IC8") (pin "6") (pinfunction "CATHODE_3_6") (pintype "bidirectional"))
      (node (ref "R23") (pin "1") (pinfunction "1_1") (pintype "passive"))
    )
    (net (code "48") (name "Net-(IC8-CATHODE_4)") (class "Default")
      (node (ref "IC8") (pin "8") (pinfunction "CATHODE_4_8") (pintype "bidirectional"))
      (node (ref "R24") (pin "1") (pinfunction "1_1") (pintype "passive"))
    )
    (net (code "49") (name "Net-(IC9-CATHODE_1)") (class "Default")
      (node (ref "IC9") (pin "2") (pinfunction "CATHODE_1_2") (pintype "bidirectional"))
      (node (ref "R29") (pin "1") (pinfunction "1_1") (pintype "passive"))
    )
    (net (code "50") (name "Net-(IC9-CATHODE_2)") (class "Default")
      (node (ref "IC9") (pin "4") (pinfunction "CATHODE_2_4") (pintype "bidirectional"))
      (node (ref "R30") (pin "1") (pinfunction "1_1") (pintype "passive"))
    )
    (net (code "51") (name "Net-(IC9-CATHODE_3)") (class "Default")
      (node (ref "IC9") (pin "6") (pinfunction "CATHODE_3_6") (pintype "bidirectional"))
      (node (ref "R31") (pin "1") (pinfunction "1_1") (pintype "passive"))
    )
    (net (code "52") (name "Net-(IC9-CATHODE_4)") (class "Default")
      (node (ref "IC9") (pin "8") (pinfunction "CATHODE_4_8") (pintype "bidirectional"))
      (node (ref "R32") (pin "1") (pinfunction "1_1") (pintype "passive"))
    )
    (net (code "53") (name "Net-(LED1-PadK)") (class "Default")
      (node (ref "LED1") (pin "K") (pinfunction "K_K") (pintype "passive"))
      (node (ref "R46") (pin "1") (pinfunction "1_1") (pintype "passive"))
    )
    (net (code "54") (name "Net-(LED2-PadA)") (class "Default")
      (node (ref "LED2") (pin "A") (pinfunction "A_A") (pintype "passive"))
      (node (ref "R2") (pin "2") (pinfunction "2_2") (pintype "passive"))
    )
    (net (code "55") (name "Net-(LED3-PadK)") (class "Default")
      (node (ref "LED3") (pin "K") (pinfunction "K_K") (pintype "passive"))
      (node (ref "R3") (pin "1") (pinfunction "1_1") (pintype "passive"))
    )
    (net (code "56") (name "Net-(LED4-PadK)") (class "Default")
      (node (ref "LED4") (pin "K") (pinfunction "K_K") (pintype "passive"))
      (node (ref "R47") (pin "1") (pinfunction "1_1") (pintype "passive"))
    )
    (net (code "57") (name "Net-(LED5-PadK)") (class "Default")
      (node (ref "LED5") (pin "K") (pinfunction "K_K") (pintype "passive"))
      (node (ref "R48") (pin "1") (pinfunction "1_1") (pintype "passive"))
    )
    (net (code "58") (name "Net-(LED6-PadK)") (class "Default")
      (node (ref "LED6") (pin "K") (pinfunction "K_K") (pintype "passive"))
      (node (ref "R78") (pin "1") (pinfunction "1_1") (pintype "passive"))
    )
    (net (code "59") (name "Net-(LED7-PadA)") (class "Default")
      (node (ref "LED7") (pin "A") (pinfunction "A_A") (pintype "passive"))
      (node (ref "R93") (pin "2") (pinfunction "2_2") (pintype "passive"))
    )
    (net (code "60") (name "Net-(LED8-PadK)") (class "Default")
      (node (ref "LED8") (pin "K") (pinfunction "K_K") (pintype "passive"))
      (node (ref "R79") (pin "1") (pinfunction "1_1") (pintype "passive"))
    )
    (net (code "61") (name "Net-(LED9-PadK)") (class "Default")
      (node (ref "LED9") (pin "K") (pinfunction "K_K") (pintype "passive"))
      (node (ref "R49") (pin "1") (pinfunction "1_1") (pintype "passive"))
    )
    (net (code "62") (name "Net-(LED10-PadK)") (class "Default")
      (node (ref "LED10") (pin "K") (pinfunction "K_K") (pintype "passive"))
      (node (ref "R50") (pin "1") (pinfunction "1_1") (pintype "passive"))
    )
    (net (code "63") (name "Net-(LED11-PadK)") (class "Default")
      (node (ref "LED11") (pin "K") (pinfunction "K_K") (pintype "passive"))
      (node (ref "R51") (pin "1") (pinfunction "1_1") (pintype "passive"))
    )
    (net (code "64") (name "Net-(LED12-PadK)") (class "Default")
      (node (ref "LED12") (pin "K") (pinfunction "K_K") (pintype "passive"))
      (node (ref "R52") (pin "1") (pinfunction "1_1") (pintype "passive"))
    )
    (net (code "65") (name "Net-(LED13-PadK)") (class "Default")
      (node (ref "LED13") (pin "K") (pinfunction "K_K") (pintype "passive"))
      (node (ref "R53") (pin "1") (pinfunction "1_1") (pintype "passive"))
    )
    (net (code "66") (name "Net-(LED14-PadA)") (class "Default")
      (node (ref "LED14") (pin "A") (pinfunction "A_A") (pintype "passive"))
      (node (ref "R60") (pin "2") (pinfunction "2_2") (pintype "passive"))
    )
    (net (code "67") (name "Net-(LED15-PadA)") (class "Default")
      (node (ref "LED15") (pin "A") (pinfunction "A_A") (pintype "passive"))
      (node (ref "R62") (pin "2") (pinfunction "2_2") (pintype "passive"))
    )
    (net (code "68") (name "Net-(LED16-PadA)") (class "Default")
      (node (ref "LED16") (pin "A") (pinfunction "A_A") (pintype "passive"))
      (node (ref "R64") (pin "2") (pinfunction "2_2") (pintype "passive"))
    )
    (net (code "69") (name "Net-(LED17-PadA)") (class "Default")
      (node (ref "LED17") (pin "A") (pinfunction "A_A") (pintype "passive"))
      (node (ref "R66") (pin "2") (pinfunction "2_2") (pintype "passive"))
    )
    (net (code "70") (name "Net-(LED18-PadK)") (class "Default")
      (node (ref "LED18") (pin "K") (pinfunction "K_K") (pintype "passive"))
      (node (ref "R80") (pin "1") (pinfunction "1_1") (pintype "passive"))
    )
    (net (code "71") (name "Net-(LED19-PadK)") (class "Default")
      (node (ref "LED19") (pin "K") (pinfunction "K_K") (pintype "passive"))
      (node (ref "R81") (pin "1") (pinfunction "1_1") (pintype "passive"))
    )
    (net (code "72") (name "Net-(LED20-PadK)") (class "Default")
      (node (ref "LED20") (pin "K") (pinfunction "K_K") (pintype "passive"))
      (node (ref "R82") (pin "1") (pinfunction "1_1") (pintype "passive"))
    )
    (net (code "73") (name "Net-(LED21-PadA)") (class "Default")
      (node (ref "LED21") (pin "A") (pinfunction "A_A") (pintype "passive"))
      (node (ref "R71") (pin "2") (pinfunction "2_2") (pintype "passive"))
    )
    (net (code "74") (name "Net-(LED22-PadA)") (class "Default")
      (node (ref "LED22") (pin "A") (pinfunction "A_A") (pintype "passive"))
      (node (ref "R73") (pin "2") (pinfunction "2_2") (pintype "passive"))
    )
    (net (code "75") (name "Net-(LED23-PadA)") (class "Default")
      (node (ref "LED23") (pin "A") (pinfunction "A_A") (pintype "passive"))
      (node (ref "R75") (pin "2") (pinfunction "2_2") (pintype "passive"))
    )
    (net (code "76") (name "Net-(LED24-PadA)") (class "Default")
      (node (ref "LED24") (pin "A") (pinfunction "A_A") (pintype "passive"))
      (node (ref "R45") (pin "2") (pinfunction "2_2") (pintype "passive"))
    )
    (net (code "77") (name "Net-(LED25-PadA)") (class "Default")
      (node (ref "LED25") (pin "A") (pinfunction "A_A") (pintype "passive"))
      (node (ref "R55") (pin "2") (pinfunction "2_2") (pintype "passive"))
    )
    (net (code "78") (name "Net-(LED26-PadA)") (class "Default")
      (node (ref "LED26") (pin "A") (pinfunction "A_A") (pintype "passive"))
      (node (ref "R57") (pin "2") (pinfunction "2_2") (pintype "passive"))
    )
    (net (code "79") (name "Net-(LED27-PadA)") (class "Default")
      (node (ref "LED27") (pin "A") (pinfunction "A_A") (pintype "passive"))
      (node (ref "R67") (pin "2") (pinfunction "2_2") (pintype "passive"))
    )
    (net (code "80") (name "Net-(LED28-PadK)") (class "Default")
      (node (ref "LED28") (pin "K") (pinfunction "K_K") (pintype "passive"))
      (node (ref "R83") (pin "1") (pinfunction "1_1") (pintype "passive"))
    )
    (net (code "81") (name "Net-(LED29-PadA)") (class "Default")
      (node (ref "LED29") (pin "A") (pinfunction "A_A") (pintype "passive"))
      (node (ref "R10") (pin "2") (pinfunction "2_2") (pintype "passive"))
    )
    (net (code "82") (name "Net-(LED30-PadK)") (class "Default")
      (node (ref "LED30") (pin "K") (pinfunction "K_K") (pintype "passive"))
      (node (ref "R84") (pin "1") (pinfunction "1_1") (pintype "passive"))
    )
    (net (code "83") (name "Net-(LED31-PadK)") (class "Default")
      (node (ref "LED31") (pin "K") (pinfunction "K_K") (pintype "passive"))
      (node (ref "R85") (pin "1") (pinfunction "1_1") (pintype "passive"))
    )
    (net (code "84") (name "Net-(LED32-PadA)") (class "Default")
      (node (ref "LED32") (pin "A") (pinfunction "A_A") (pintype "passive"))
      (node (ref "R95") (pin "2") (pinfunction "2_2") (pintype "passive"))
    )
    (net (code "85") (name "Net-(LED33-PadA)") (class "Default")
      (node (ref "LED33") (pin "A") (pinfunction "A_A") (pintype "passive"))
      (node (ref "R97") (pin "2") (pinfunction "2_2") (pintype "passive"))
    )
    (net (code "86") (name "Net-(LED34-PadA)") (class "Default")
      (node (ref "LED34") (pin "A") (pinfunction "A_A") (pintype "passive"))
      (node (ref "R99") (pin "2") (pinfunction "2_2") (pintype "passive"))
    )
    (net (code "87") (name "Net-(LED35-PadA)") (class "Default")
      (node (ref "LED35") (pin "A") (pinfunction "A_A") (pintype "passive"))
      (node (ref "R77") (pin "2") (pinfunction "2_2") (pintype "passive"))
    )
    (net (code "88") (name "Net-(LED36-PadA)") (class "Default")
      (node (ref "LED36") (pin "A") (pinfunction "A_A") (pintype "passive"))
      (node (ref "R87") (pin "2") (pinfunction "2_2") (pintype "passive"))
    )
    (net (code "89") (name "Net-(LED37-PadA)") (class "Default")
      (node (ref "LED37") (pin "A") (pinfunction "A_A") (pintype "passive"))
      (node (ref "R89") (pin "2") (pinfunction "2_2") (pintype "passive"))
    )
    (net (code "90") (name "Net-(LED38-PadA)") (class "Default")
      (node (ref "LED38") (pin "A") (pinfunction "A_A") (pintype "passive"))
      (node (ref "R91") (pin "2") (pinfunction "2_2") (pintype "passive"))
    )
    (net (code "91") (name "Net-(LED39-PadA)") (class "Default")
      (node (ref "LED39") (pin "A") (pinfunction "A_A") (pintype "passive"))
      (node (ref "R69") (pin "2") (pinfunction "2_2") (pintype "passive"))
    )
    (net (code "92") (name "Net-(LED40-PadA)") (class "Default")
      (node (ref "LED40") (pin "A") (pinfunction "A_A") (pintype "passive"))
      (node (ref "R20") (pin "2") (pinfunction "2_2") (pintype "passive"))
    )
    (net (code "93") (name "Net-(LED41-PadK)") (class "Default")
      (node (ref "LED41") (pin "K") (pinfunction "K_K") (pintype "passive"))
      (node (ref "R25") (pin "1") (pinfunction "1_1") (pintype "passive"))
    )
    (net (code "94") (name "Net-(LED42-PadA)") (class "Default")
      (node (ref "LED42") (pin "A") (pinfunction "A_A") (pintype "passive"))
      (node (ref "R110") (pin "2") (pinfunction "2_2") (pintype "passive"))
    )
    (net (code "95") (name "Net-(LED43-PadA)") (class "Default")
      (node (ref "LED43") (pin "A") (pinfunction "A_A") (pintype "passive"))
      (node (ref "R112") (pin "2") (pinfunction "2_2") (pintype "passive"))
    )
    (net (code "96") (name "Net-(LED44-PadA)") (class "Default")
      (node (ref "LED44") (pin "A") (pinfunction "A_A") (pintype "passive"))
      (node (ref "R106") (pin "2") (pinfunction "2_2") (pintype "passive"))
    )
    (net (code "97") (name "Net-(LED45-PadA)") (class "Default")
      (node (ref "LED45") (pin "A") (pinfunction "A_A") (pintype "passive"))
      (node (ref "R108") (pin "2") (pinfunction "2_2") (pintype "passive"))
    )
    (net (code "98") (name "Net-(LED46-PadK)") (class "Default")
      (node (ref "LED46") (pin "K") (pinfunction "K_K") (pintype "passive"))
      (node (ref "R114") (pin "1") (pinfunction "1_1") (pintype "passive"))
    )
    (net (code "99") (name "Net-(LED47-PadK)") (class "Default")
      (node (ref "LED47") (pin "K") (pinfunction "K_K") (pintype "passive"))
      (node (ref "R115") (pin "1") (pinfunction "1_1") (pintype "passive"))
    )
    (net (code "100") (name "Net-(LED48-PadK)") (class "Default")
      (node (ref "LED48") (pin "K") (pinfunction "K_K") (pintype "passive"))
      (node (ref "R116") (pin "1") (pinfunction "1_1") (pintype "passive"))
    )
    (net (code "101") (name "Net-(LED49-PadK)") (class "Default")
      (node (ref "LED49") (pin "K") (pinfunction "K_K") (pintype "passive"))
      (node (ref "R117") (pin "1") (pinfunction "1_1") (pintype "passive"))
    )
    (net (code "102") (name "Net-(LED50-PadA)") (class "Default")
      (node (ref "LED50") (pin "A") (pinfunction "A_A") (pintype "passive"))
      (node (ref "R118") (pin "2") (pinfunction "2_2") (pintype "passive"))
    )
    (net (code "103") (name "Net-(LED51-G-PadK)") (class "Default")
      (node (ref "LED51-G") (pin "K") (pinfunction "K_K") (pintype "passive"))
      (node (ref "R119") (pin "1") (pinfunction "1_1") (pintype "passive"))
    )
    (net (code "104") (name "Net-(LED52-Y-PadK)") (class "Default")
      (node (ref "LED52-Y") (pin "K") (pinfunction "K_K") (pintype "passive"))
      (node (ref "R120") (pin "1") (pinfunction "1_1") (pintype "passive"))
    )
    (net (code "105") (name "Net-(Q9-D)") (class "Default")
      (node (ref "Q9") (pin "3") (pinfunction "D_3") (pintype "bidirectional"))
      (node (ref "R119") (pin "2") (pinfunction "2_2") (pintype "passive"))
    )
    (net (code "106") (name "Net-(Q9-G)") (class "Default")
      (node (ref "Q9") (pin "1") (pinfunction "G_1") (pintype "bidirectional"))
      (node (ref "R121") (pin "1") (pinfunction "1_1") (pintype "passive"))
    )
    (net (code "107") (name "Net-(Q10-D)") (class "Default")
      (node (ref "Q10") (pin "3") (pinfunction "D_3") (pintype "bidirectional"))
      (node (ref "R120") (pin "2") (pinfunction "2_2") (pintype "passive"))
    )
    (net (code "108") (name "Net-(Q10-G)") (class "Default")
      (node (ref "Q10") (pin "1") (pinfunction "G_1") (pintype "bidirectional"))
      (node (ref "R122") (pin "1") (pinfunction "1_1") (pintype "passive"))
    )
    (net (code "109") (name "Net-(TR1-G)") (class "Default")
      (node (ref "R68") (pin "2") (pinfunction "2_2") (pintype "passive"))
      (node (ref "TR1") (pin "1") (pinfunction "G_1") (pintype "bidirectional"))
    )
    (net (code "110") (name "Net-(TR2-G)") (class "Default")
      (node (ref "R86") (pin "2") (pinfunction "2_2") (pintype "passive"))
      (node (ref "TR2") (pin "1") (pinfunction "G_1") (pintype "bidirectional"))
    )
    (net (code "111") (name "Net-(TR3-G)") (class "Default")
      (node (ref "R88") (pin "2") (pinfunction "2_2") (pintype "passive"))
      (node (ref "TR3") (pin "1") (pinfunction "G_1") (pintype "bidirectional"))
    )
    (net (code "112") (name "Net-(TR4-G)") (class "Default")
      (node (ref "R90") (pin "2") (pinfunction "2_2") (pintype "passive"))
      (node (ref "TR4") (pin "1") (pinfunction "G_1") (pintype "bidirectional"))
    )
    (net (code "113") (name "Net-(TR5-G)") (class "Default")
      (node (ref "R70") (pin "2") (pinfunction "2_2") (pintype "passive"))
      (node (ref "TR5") (pin "1") (pinfunction "G_1") (pintype "bidirectional"))
    )
    (net (code "114") (name "Net-(TR6-G)") (class "Default")
      (node (ref "R72") (pin "2") (pinfunction "2_2") (pintype "passive"))
      (node (ref "TR6") (pin "1") (pinfunction "G_1") (pintype "bidirectional"))
    )
    (net (code "115") (name "Net-(TR7-G)") (class "Default")
      (node (ref "R74") (pin "2") (pinfunction "2_2") (pintype "passive"))
      (node (ref "TR7") (pin "1") (pinfunction "G_1") (pintype "bidirectional"))
    )
    (net (code "116") (name "Net-(TR8-G)") (class "Default")
      (node (ref "R76") (pin "2") (pinfunction "2_2") (pintype "passive"))
      (node (ref "TR8") (pin "1") (pinfunction "G_1") (pintype "bidirectional"))
    )
    (net (code "117") (name "Net-(TR9-G)") (class "Default")
      (node (ref "R54") (pin "2") (pinfunction "2_2") (pintype "passive"))
      (node (ref "TR9") (pin "1") (pinfunction "G_1") (pintype "bidirectional"))
    )
    (net (code "118") (name "Net-(TR10-G)") (class "Default")
      (node (ref "R56") (pin "2") (pinfunction "2_2") (pintype "passive"))
      (node (ref "TR10") (pin "1") (pinfunction "G_1") (pintype "bidirectional"))
    )
    (net (code "119") (name "Net-(TR11-G)") (class "Default")
      (node (ref "R58") (pin "2") (pinfunction "2_2") (pintype "passive"))
      (node (ref "TR11") (pin "1") (pinfunction "G_1") (pintype "bidirectional"))
    )
    (net (code "120") (name "Net-(TR12-D)") (class "Default")
      (node (ref "LED14") (pin "K") (pinfunction "K_K") (pintype "passive"))
      (node (ref "TR12") (pin "3") (pinfunction "D_3") (pintype "bidirectional"))
    )
    (net (code "121") (name "Net-(TR12-G)") (class "Default")
      (node (ref "R59") (pin "2") (pinfunction "2_2") (pintype "passive"))
      (node (ref "TR12") (pin "1") (pinfunction "G_1") (pintype "bidirectional"))
    )
    (net (code "122") (name "Net-(TR13-D)") (class "Default")
      (node (ref "LED15") (pin "K") (pinfunction "K_K") (pintype "passive"))
      (node (ref "TR13") (pin "3") (pinfunction "D_3") (pintype "bidirectional"))
    )
    (net (code "123") (name "Net-(TR13-G)") (class "Default")
      (node (ref "R61") (pin "2") (pinfunction "2_2") (pintype "passive"))
      (node (ref "TR13") (pin "1") (pinfunction "G_1") (pintype "bidirectional"))
    )
    (net (code "124") (name "Net-(TR14-D)") (class "Default")
      (node (ref "LED16") (pin "K") (pinfunction "K_K") (pintype "passive"))
      (node (ref "TR14") (pin "3") (pinfunction "D_3") (pintype "bidirectional"))
    )
    (net (code "125") (name "Net-(TR14-G)") (class "Default")
      (node (ref "R63") (pin "2") (pinfunction "2_2") (pintype "passive"))
      (node (ref "TR14") (pin "1") (pinfunction "G_1") (pintype "bidirectional"))
    )
    (net (code "126") (name "Net-(TR15-G)") (class "Default")
      (node (ref "R92") (pin "2") (pinfunction "2_2") (pintype "passive"))
      (node (ref "TR15") (pin "1") (pinfunction "G_1") (pintype "bidirectional"))
    )
    (net (code "127") (name "Net-(TR16-G)") (class "Default")
      (node (ref "R94") (pin "2") (pinfunction "2_2") (pintype "passive"))
      (node (ref "TR16") (pin "1") (pinfunction "G_1") (pintype "bidirectional"))
    )
    (net (code "128") (name "Net-(TR17-D)") (class "Default")
      (node (ref "LED17") (pin "K") (pinfunction "K_K") (pintype "passive"))
      (node (ref "TR17") (pin "3") (pinfunction "D_3") (pintype "bidirectional"))
    )
    (net (code "129") (name "Net-(TR17-G)") (class "Default")
      (node (ref "R65") (pin "2") (pinfunction "2_2") (pintype "passive"))
      (node (ref "TR17") (pin "1") (pinfunction "G_1") (pintype "bidirectional"))
    )
    (net (code "130") (name "Net-(TR18-G)") (class "Default")
      (node (ref "R96") (pin "2") (pinfunction "2_2") (pintype "passive"))
      (node (ref "TR18") (pin "1") (pinfunction "G_1") (pintype "bidirectional"))
    )
    (net (code "131") (name "Net-(TR19-G)") (class "Default")
      (node (ref "R98") (pin "2") (pinfunction "2_2") (pintype "passive"))
      (node (ref "TR19") (pin "1") (pinfunction "G_1") (pintype "bidirectional"))
    )
    (net (code "132") (name "Net-(TR20-G)") (class "Default")
      (node (ref "R100") (pin "2") (pinfunction "2_2") (pintype "passive"))
      (node (ref "TR20") (pin "1") (pinfunction "G_1") (pintype "bidirectional"))
    )
    (net (code "133") (name "Net-(TR21-D)") (class "Default")
      (node (ref "LED29") (pin "K") (pinfunction "K_K") (pintype "passive"))
      (node (ref "TR21") (pin "3") (pinfunction "D_3") (pintype "bidirectional"))
    )
    (net (code "134") (name "Net-(TR21-G)") (class "Default")
      (node (ref "R9") (pin "2") (pinfunction "2_2") (pintype "passive"))
      (node (ref "TR21") (pin "1") (pinfunction "G_1") (pintype "bidirectional"))
    )
    (net (code "135") (name "Net-(TR22-D)") (class "Default")
      (node (ref "LED40") (pin "K") (pinfunction "K_K") (pintype "passive"))
      (node (ref "TR22") (pin "3") (pinfunction "D_3") (pintype "bidirectional"))
    )
    (net (code "136") (name "Net-(TR22-G)") (class "Default")
      (node (ref "R11") (pin "2") (pinfunction "2_2") (pintype "passive"))
      (node (ref "TR22") (pin "1") (pinfunction "G_1") (pintype "bidirectional"))
    )
    (net (code "137") (name "Net-(TR23-G)") (class "Default")
      (node (ref "R107") (pin "2") (pinfunction "2_2") (pintype "passive"))
      (node (ref "TR23") (pin "1") (pinfunction "G_1") (pintype "bidirectional"))
    )
    (net (code "138") (name "Net-(TR24-G)") (class "Default")
      (node (ref "R109") (pin "2") (pinfunction "2_2") (pintype "passive"))
      (node (ref "TR24") (pin "1") (pinfunction "G_1") (pintype "bidirectional"))
    )
    (net (code "139") (name "Net-(TR25-G)") (class "Default")
      (node (ref "R111") (pin "2") (pinfunction "2_2") (pintype "passive"))
      (node (ref "TR25") (pin "1") (pinfunction "G_1") (pintype "bidirectional"))
    )
    (net (code "140") (name "Net-(TR26-G)") (class "Default")
      (node (ref "R113") (pin "2") (pinfunction "2_2") (pintype "passive"))
      (node (ref "TR26") (pin "1") (pinfunction "G_1") (pintype "bidirectional"))
    )
    (net (code "141") (name "PA8") (class "Default")
      (node (ref "IC1") (pin "41") (pinfunction "PA8_41") (pintype "bidirectional"))
      (node (ref "JP1") (pin "1") (pinfunction "1_1") (pintype "passive"))
    )
    (net (code "142") (name "PB5") (class "Default")
      (node (ref "IC1") (pin "57") (pinfunction "PB5_57") (pintype "bidirectional"))
      (node (ref "R61") (pin "1") (pinfunction "1_1") (pintype "passive"))
    )
    (net (code "143") (name "PB6") (class "Default")
      (node (ref "IC1") (pin "58") (pinfunction "PB6_58") (pintype "bidirectional"))
      (node (ref "R63") (pin "1") (pinfunction "1_1") (pintype "passive"))
    )
    (net (code "144") (name "PB7") (class "Default")
      (node (ref "IC1") (pin "59") (pinfunction "PB7_59") (pintype "bidirectional"))
      (node (ref "R65") (pin "1") (pinfunction "1_1") (pintype "passive"))
    )
    (net (code "145") (name "PB8") (class "Default")
      (node (ref "IC1") (pin "61") (pinfunction "PB8_61") (pintype "bidirectional"))
      (node (ref "R9") (pin "1") (pinfunction "1_1") (pintype "passive"))
    )
    (net (code "146") (name "PB12") (class "Default")
      (node (ref "IC1") (pin "33") (pinfunction "PB12_33") (pintype "bidirectional"))
      (node (ref "JP3") (pin "3") (pinfunction "3_3") (pintype "passive"))
    )
    (net (code "147") (name "PB13") (class "Default")
      (node (ref "IC1") (pin "34") (pinfunction "PB13_34") (pintype "bidirectional"))
      (node (ref "JP3") (pin "2") (pinfunction "2_2") (pintype "passive"))
    )
    (net (code "148") (name "PB14") (class "Default")
      (node (ref "IC1") (pin "35") (pinfunction "PB14_35") (pintype "bidirectional"))
      (node (ref "JP3") (pin "1") (pinfunction "1_1") (pintype "passive"))
    )
    (net (code "149") (name "PB15") (class "Default")
      (node (ref "IC1") (pin "36") (pinfunction "PB15_36") (pintype "bidirectional"))
      (node (ref "JP2") (pin "3") (pinfunction "3_3") (pintype "passive"))
    )
    (net (code "150") (name "PC6") (class "Default")
      (node (ref "IC1") (pin "37") (pinfunction "PC6_37") (pintype "bidirectional"))
      (node (ref "JP2") (pin "2") (pinfunction "2_2") (pintype "passive"))
    )
    (net (code "151") (name "PC7") (class "Default")
      (node (ref "IC1") (pin "38") (pinfunction "PC7_38") (pintype "bidirectional"))
      (node (ref "JP2") (pin "1") (pinfunction "1_1") (pintype "passive"))
    )
    (net (code "152") (name "PC8") (class "Default")
      (node (ref "IC1") (pin "39") (pinfunction "PC8_39") (pintype "bidirectional"))
      (node (ref "JP1") (pin "3") (pinfunction "3_3") (pintype "passive"))
    )
    (net (code "153") (name "PC9") (class "Default")
      (node (ref "IC1") (pin "40") (pinfunction "PC9_40") (pintype "bidirectional"))
      (node (ref "JP1") (pin "2") (pinfunction "2_2") (pintype "passive"))
    )
    (net (code "154") (name "PC13") (class "Default")
      (node (ref "IC1") (pin "2") (pinfunction "PC13_2") (pintype "bidirectional"))
      (node (ref "R11") (pin "1") (pinfunction "1_1") (pintype "passive"))
    )
    (net (code "155") (name "PD2") (class "Default")
      (node (ref "IC1") (pin "54") (pinfunction "PD2_54") (pintype "bidirectional"))
      (node (ref "R59") (pin "1") (pinfunction "1_1") (pintype "passive"))
    )
    (net (code "156") (name "SCL") (class "Default")
      (node (ref "IC1") (pin "42") (pinfunction "PA9_42") (pintype "bidirectional"))
      (node (ref "X19") (pin "2") (pinfunction "2_2") (pintype "passive"))
    )
    (net (code "157") (name "SDA") (class "Default")
      (node (ref "IC1") (pin "43") (pinfunction "PA10_43") (pintype "bidirectional"))
      (node (ref "X19") (pin "1") (pinfunction "1_1") (pintype "passive"))
    )
    (net (code "158") (name "SERVO_1") (class "Default")
      (node (ref "IC9") (pin "15") (pinfunction "EMITTER_4_15") (pintype "bidirectional"))
      (node (ref "LED6") (pin "A") (pinfunction "A_A") (pintype "passive"))
      (node (ref "R33") (pin "2") (pinfunction "2_2") (pintype "passive"))
      (node (ref "X24") (pin "2") (pinfunction "2_2") (pintype "passive"))
    )
    (net (code "159") (name "SERVO_2") (class "Default")
      (node (ref "IC9") (pin "13") (pinfunction "EMITTER_3_13") (pintype "bidirectional"))
      (node (ref "LED8") (pin "A") (pinfunction "A_A") (pintype "passive"))
      (node (ref "R34") (pin "2") (pinfunction "2_2") (pintype "passive"))
      (node (ref "X23") (pin "2") (pinfunction "2_2") (pintype "passive"))
    )
    (net (code "160") (name "SERVO_3") (class "Default")
      (node (ref "IC9") (pin "11") (pinfunction "EMITTER_2_11") (pintype "bidirectional"))
      (node (ref "LED18") (pin "A") (pinfunction "A_A") (pintype "passive"))
      (node (ref "R35") (pin "2") (pinfunction "2_2") (pintype "passive"))
      (node (ref "X21") (pin "2") (pinfunction "2_2") (pintype "passive"))
    )
    (net (code "161") (name "SERVO_4") (class "Default")
      (node (ref "IC9") (pin "9") (pinfunction "EMITTER_1_9") (pintype "bidirectional"))
      (node (ref "LED19") (pin "A") (pinfunction "A_A") (pintype "passive"))
      (node (ref "R36") (pin "2") (pinfunction "2_2") (pintype "passive"))
      (node (ref "X20") (pin "2") (pinfunction "2_2") (pintype "passive"))
    )
    (net (code "162") (name "SERVO_5") (class "Default")
      (node (ref "IC4") (pin "15") (pinfunction "EMITTER_4_15") (pintype "bidirectional"))
      (node (ref "LED20") (pin "A") (pinfunction "A_A") (pintype "passive"))
      (node (ref "R41") (pin "2") (pinfunction "2_2") (pintype "passive"))
      (node (ref "X17") (pin "2") (pinfunction "2_2") (pintype "passive"))
    )
    (net (code "163") (name "SERVO_6") (class "Default")
      (node (ref "IC4") (pin "13") (pinfunction "EMITTER_3_13") (pintype "bidirectional"))
      (node (ref "LED28") (pin "A") (pinfunction "A_A") (pintype "passive"))
      (node (ref "R42") (pin "2") (pinfunction "2_2") (pintype "passive"))
      (node (ref "X16") (pin "2") (pinfunction "2_2") (pintype "passive"))
    )
    (net (code "164") (name "SERVO_7") (class "Default")
      (node (ref "IC4") (pin "11") (pinfunction "EMITTER_2_11") (pintype "bidirectional"))
      (node (ref "LED30") (pin "A") (pinfunction "A_A") (pintype "passive"))
      (node (ref "R43") (pin "2") (pinfunction "2_2") (pintype "passive"))
      (node (ref "X3") (pin "2") (pinfunction "2_2") (pintype "passive"))
    )
    (net (code "165") (name "SERVO_8") (class "Default")
      (node (ref "IC4") (pin "9") (pinfunction "EMITTER_1_9") (pintype "bidirectional"))
      (node (ref "LED31") (pin "A") (pinfunction "A_A") (pintype "passive"))
      (node (ref "R44") (pin "2") (pinfunction "2_2") (pintype "passive"))
      (node (ref "X2") (pin "2") (pinfunction "2_2") (pintype "passive"))
    )
    (net (code "166") (name "SERVO_9") (class "Default")
      (node (ref "IC5") (pin "15") (pinfunction "EMITTER_4_15") (pintype "bidirectional"))
      (node (ref "LED46") (pin "A") (pinfunction "A_A") (pintype "passive"))
      (node (ref "R102") (pin "2") (pinfunction "2_2") (pintype "passive"))
      (node (ref "X15") (pin "2") (pinfunction "2_2") (pintype "passive"))
    )
    (net (code "167") (name "SERVO_10") (class "Default")
      (node (ref "IC5") (pin "13") (pinfunction "EMITTER_3_13") (pintype "bidirectional"))
      (node (ref "LED47") (pin "A") (pinfunction "A_A") (pintype "passive"))
      (node (ref "R103") (pin "2") (pinfunction "2_2") (pintype "passive"))
      (node (ref "X14") (pin "2") (pinfunction "2_2") (pintype "passive"))
    )
    (net (code "168") (name "SERVO_11") (class "Default")
      (node (ref "IC5") (pin "11") (pinfunction "EMITTER_2_11") (pintype "bidirectional"))
      (node (ref "LED48") (pin "A") (pinfunction "A_A") (pintype "passive"))
      (node (ref "R104") (pin "2") (pinfunction "2_2") (pintype "passive"))
      (node (ref "X13") (pin "2") (pinfunction "2_2") (pintype "passive"))
    )
    (net (code "169") (name "SERVO_12") (class "Default")
      (node (ref "IC5") (pin "9") (pinfunction "EMITTER_1_9") (pintype "bidirectional"))
      (node (ref "LED49") (pin "A") (pinfunction "A_A") (pintype "passive"))
      (node (ref "R105") (pin "2") (pinfunction "2_2") (pintype "passive"))
      (node (ref "X4") (pin "2") (pinfunction "2_2") (pintype "passive"))
    )
    (net (code "170") (name "SIGNAL-SE_1") (class "Default")
      (node (ref "IC1") (pin "30") (pinfunction "PB11_30") (pintype "bidirectional"))
      (node (ref "R86") (pin "1") (pinfunction "1_1") (pintype "passive"))
    )
    (net (code "171") (name "SIGNAL-SE_2") (class "Default")
      (node (ref "IC1") (pin "29") (pinfunction "PB10_29") (pintype "bidirectional"))
      (node (ref "R90") (pin "1") (pinfunction "1_1") (pintype "passive"))
    )
    (net (code "172") (name "SIGNAL-SE_3") (class "Default")
      (node (ref "IC1") (pin "27") (pinfunction "PB1_27") (pintype "bidirectional"))
      (node (ref "R107") (pin "1") (pinfunction "1_1") (pintype "passive"))
    )
    (net (code "173") (name "SIGNAL-SE_4") (class "Default")
      (node (ref "IC1") (pin "26") (pinfunction "PB0_26") (pintype "bidirectional"))
      (node (ref "R94") (pin "1") (pinfunction "1_1") (pintype "passive"))
    )
    (net (code "174") (name "SIGNAL-SE_5") (class "Default")
      (node (ref "IC1") (pin "23") (pinfunction "PA7_23") (pintype "bidirectional"))
      (node (ref "R98") (pin "1") (pinfunction "1_1") (pintype "passive"))
    )
    (net (code "175") (name "SIGNAL-SE_6") (class "Default")
      (node (ref "IC1") (pin "22") (pinfunction "PA6_22") (pintype "bidirectional"))
      (node (ref "R111") (pin "1") (pinfunction "1_1") (pintype "passive"))
    )
    (net (code "176") (name "SIGNAL-SE_7") (class "Default")
      (node (ref "IC1") (pin "21") (pinfunction "PA5_21") (pintype "bidirectional"))
      (node (ref "R88") (pin "1") (pinfunction "1_1") (pintype "passive"))
    )
    (net (code "177") (name "SIGNAL-SE_8") (class "Default")
      (node (ref "IC1") (pin "20") (pinfunction "PA4_20") (pintype "bidirectional"))
      (node (ref "R92") (pin "1") (pinfunction "1_1") (pintype "passive"))
    )
    (net (code "178") (name "SIGNAL-SE_9") (class "Default")
      (node (ref "IC1") (pin "17") (pinfunction "PA3_17") (pintype "bidirectional"))
      (node (ref "R109") (pin "1") (pinfunction "1_1") (pintype "passive"))
    )
    (net (code "179") (name "SIGNAL-SE_10") (class "Default")
      (node (ref "IC1") (pin "16") (pinfunction "PA2_16") (pintype "bidirectional"))
      (node (ref "R96") (pin "1") (pinfunction "1_1") (pintype "passive"))
    )
    (net (code "180") (name "SIGNAL-SE_11") (class "Default")
      (node (ref "IC1") (pin "15") (pinfunction "PA1_15") (pintype "bidirectional"))
      (node (ref "R100") (pin "1") (pinfunction "1_1") (pintype "passive"))
    )
    (net (code "181") (name "SIGNAL-SE_12") (class "Default")
      (node (ref "IC1") (pin "62") (pinfunction "PB9_62") (pintype "bidirectional"))
      (node (ref "R113") (pin "1") (pinfunction "1_1") (pintype "passive"))
    )
    (net (code "182") (name "SIGNAL-SO_1") (class "Default")
      (node (ref "IC1") (pin "11") (pinfunction "PC3_11") (pintype "bidirectional"))
      (node (ref "R54") (pin "1") (pinfunction "1_1") (pintype "passive"))
    )
    (net (code "183") (name "SIGNAL-SO_2") (class "Default")
      (node (ref "IC1") (pin "10") (pinfunction "PC2_10") (pintype "bidirectional"))
      (node (ref "R56") (pin "1") (pinfunction "1_1") (pintype "passive"))
    )
    (net (code "184") (name "SIGNAL-SO_3") (class "Default")
      (node (ref "IC1") (pin "9") (pinfunction "PC1_9") (pintype "bidirectional"))
      (node (ref "R58") (pin "1") (pinfunction "1_1") (pintype "passive"))
    )
    (net (code "185") (name "SIGNAL-SO_4") (class "Default")
      (node (ref "IC1") (pin "8") (pinfunction "PC0_8") (pintype "bidirectional"))
      (node (ref "R68") (pin "1") (pinfunction "1_1") (pintype "passive"))
    )
    (net (code "186") (name "SIGNAL-SO_5") (class "Default")
      (node (ref "IC1") (pin "6") (pinfunction "PF1/OSC_OUT_6") (pintype "bidirectional"))
      (node (ref "R70") (pin "1") (pinfunction "1_1") (pintype "passive"))
    )
    (net (code "187") (name "SIGNAL-SO_6") (class "Default")
      (node (ref "IC1") (pin "5") (pinfunction "PF0/OSC_IN_5") (pintype "bidirectional"))
      (node (ref "R72") (pin "1") (pinfunction "1_1") (pintype "passive"))
    )
    (net (code "188") (name "SIGNAL-SO_7") (class "Default")
      (node (ref "IC1") (pin "4") (pinfunction "PC15/OSC32_OUT_4") (pintype "bidirectional"))
      (node (ref "R74") (pin "1") (pinfunction "1_1") (pintype "passive"))
    )
    (net (code "189") (name "SIGNAL-SO_8") (class "Default")
      (node (ref "IC1") (pin "3") (pinfunction "PC14/OSC32_IN_3") (pintype "bidirectional"))
      (node (ref "R76") (pin "1") (pinfunction "1_1") (pintype "passive"))
    )
    (net (code "190") (name "SIGNAL_N1") (class "Default")
      (node (ref "IC6") (pin "1") (pinfunction "I1_1") (pintype "bidirectional"))
      (node (ref "IC7") (pin "15") (pinfunction "EMITTER_4_15") (pintype "bidirectional"))
      (node (ref "R12") (pin "2") (pinfunction "2_2") (pintype "passive"))
    )
    (net (code "191") (name "SIGNAL_N2") (class "Default")
      (node (ref "IC6") (pin "2") (pinfunction "I2_2") (pintype "bidirectional"))
      (node (ref "IC7") (pin "13") (pinfunction "EMITTER_3_13") (pintype "bidirectional"))
      (node (ref "R13") (pin "2") (pinfunction "2_2") (pintype "passive"))
    )
    (net (code "192") (name "SIGNAL_N3") (class "Default")
      (node (ref "IC6") (pin "3") (pinfunction "I3_3") (pintype "bidirectional"))
      (node (ref "IC7") (pin "11") (pinfunction "EMITTER_2_11") (pintype "bidirectional"))
      (node (ref "R14") (pin "2") (pinfunction "2_2") (pintype "passive"))
    )
    (net (code "193") (name "SIGNAL_N4") (class "Default")
      (node (ref "IC6") (pin "4") (pinfunction "I4_4") (pintype "bidirectional"))
      (node (ref "IC7") (pin "9") (pinfunction "EMITTER_1_9") (pintype "bidirectional"))
      (node (ref "R15") (pin "2") (pinfunction "2_2") (pintype "passive"))
    )
    (net (code "194") (name "SIGNAL_N5") (class "Default")
      (node (ref "IC6") (pin "5") (pinfunction "I5_5") (pintype "bidirectional"))
      (node (ref "IC8") (pin "15") (pinfunction "EMITTER_4_15") (pintype "bidirectional"))
      (node (ref "R16") (pin "2") (pinfunction "2_2") (pintype "passive"))
    )
    (net (code "195") (name "SIGNAL_N6") (class "Default")
      (node (ref "IC6") (pin "6") (pinfunction "I6_6") (pintype "bidirectional"))
      (node (ref "IC8") (pin "13") (pinfunction "EMITTER_3_13") (pintype "bidirectional"))
      (node (ref "R17") (pin "2") (pinfunction "2_2") (pintype "passive"))
    )
    (net (code "196") (name "SIGNAL_N7") (class "Default")
      (node (ref "IC6") (pin "7") (pinfunction "I7_7") (pintype "bidirectional"))
      (node (ref "IC8") (pin "11") (pinfunction "EMITTER_2_11") (pintype "bidirectional"))
      (node (ref "R18") (pin "2") (pinfunction "2_2") (pintype "passive"))
    )
    (net (code "197") (name "SIGNAL_N8") (class "Default")
      (node (ref "IC6") (pin "8") (pinfunction "I8_8") (pintype "bidirectional"))
      (node (ref "IC8") (pin "9") (pinfunction "EMITTER_1_9") (pintype "bidirectional"))
      (node (ref "R19") (pin "2") (pinfunction "2_2") (pintype "passive"))
    )
    (net (code "198") (name "SOLENOID_1") (class "Default")
      (node (ref "IC6") (pin "18") (pinfunction "O1_18") (pintype "bidirectional"))
      (node (ref "LED1") (pin "A") (pinfunction "A_A") (pintype "passive"))
      (node (ref "X5") (pin "2") (pinfunction "2_2") (pintype "passive"))
    )
    (net (code "199") (name "SOLENOID_2") (class "Default")
      (node (ref "IC6") (pin "17") (pinfunction "O2_17") (pintype "bidirectional"))
      (node (ref "LED4") (pin "A") (pinfunction "A_A") (pintype "passive"))
      (node (ref "X6") (pin "2") (pinfunction "2_2") (pintype "passive"))
    )
    (net (code "200") (name "SOLENOID_3") (class "Default")
      (node (ref "IC6") (pin "16") (pinfunction "O3_16") (pintype "bidirectional"))
      (node (ref "LED5") (pin "A") (pinfunction "A_A") (pintype "passive"))
      (node (ref "X7") (pin "2") (pinfunction "2_2") (pintype "passive"))
    )
    (net (code "201") (name "SOLENOID_4") (class "Default")
      (node (ref "IC6") (pin "15") (pinfunction "O4_15") (pintype "bidirectional"))
      (node (ref "LED9") (pin "A") (pinfunction "A_A") (pintype "passive"))
      (node (ref "X1") (pin "2") (pinfunction "2_2") (pintype "passive"))
    )
    (net (code "202") (name "SOLENOID_5") (class "Default")
      (node (ref "IC6") (pin "14") (pinfunction "O5_14") (pintype "bidirectional"))
      (node (ref "LED10") (pin "A") (pinfunction "A_A") (pintype "passive"))
      (node (ref "X9") (pin "2") (pinfunction "2_2") (pintype "passive"))
    )
    (net (code "203") (name "SOLENOID_6") (class "Default")
      (node (ref "IC6") (pin "13") (pinfunction "O6_13") (pintype "bidirectional"))
      (node (ref "LED11") (pin "A") (pinfunction "A_A") (pintype "passive"))
      (node (ref "X10") (pin "2") (pinfunction "2_2") (pintype "passive"))
    )
    (net (code "204") (name "SOLENOID_7") (class "Default")
      (node (ref "IC6") (pin "12") (pinfunction "O7_12") (pintype "bidirectional"))
      (node (ref "LED12") (pin "A") (pinfunction "A_A") (pintype "passive"))
      (node (ref "X11") (pin "2") (pinfunction "2_2") (pintype "passive"))
    )
    (net (code "205") (name "SOLENOID_8") (class "Default")
      (node (ref "IC6") (pin "11") (pinfunction "O8_11") (pintype "bidirectional"))
      (node (ref "LED13") (pin "A") (pinfunction "A_A") (pintype "passive"))
      (node (ref "X12") (pin "2") (pinfunction "2_2") (pintype "passive"))
    )
    (net (code "206") (name "SPI_MISO") (class "Default")
      (node (ref "IC1") (pin "52") (pinfunction "PC11_52") (pintype "bidirectional"))
      (node (ref "X8") (pin "2") (pinfunction "2_2") (pintype "passive"))
    )
    (net (code "207") (name "SPI_MOSI") (class "Default")
      (node (ref "IC1") (pin "53") (pinfunction "PC12_53") (pintype "bidirectional"))
      (node (ref "X8") (pin "1") (pinfunction "1_1") (pintype "passive"))
    )
    (net (code "208") (name "SPI_NSS") (class "Default")
      (node (ref "IC1") (pin "50") (pinfunction "PA15_50") (pintype "bidirectional"))
      (node (ref "X8") (pin "4") (pinfunction "4_4") (pintype "passive"))
    )
    (net (code "209") (name "SPI_SCK") (class "Default")
      (node (ref "IC1") (pin "51") (pinfunction "PC10_51") (pintype "bidirectional"))
      (node (ref "X8") (pin "3") (pinfunction "3_3") (pintype "passive"))
    )
    (net (code "210") (name "SWCLK") (class "Default")
      (node (ref "IC1") (pin "49") (pinfunction "PA14_49") (pintype "bidirectional"))
      (node (ref "SL1") (pin "2") (pinfunction "2_2") (pintype "passive"))
    )
    (net (code "211") (name "SWDIO") (class "Default")
      (node (ref "IC1") (pin "46") (pinfunction "PA13_46") (pintype "bidirectional"))
      (node (ref "SL1") (pin "4") (pinfunction "4_4") (pintype "passive"))
    )
    (net (code "212") (name "SWO") (class "Default")
      (node (ref "SL1") (pin "6") (pinfunction "6_6") (pintype "passive"))
    )
    (net (code "213") (name "USART_RX") (class "Default")
      (node (ref "IC1") (pin "56") (pinfunction "PB4_56") (pintype "bidirectional"))
      (node (ref "X18") (pin "2") (pinfunction "2_2") (pintype "passive"))
    )
    (net (code "214") (name "USART_TX") (class "Default")
      (node (ref "IC1") (pin "55") (pinfunction "PB3_55") (pintype "bidirectional"))
      (node (ref "X18") (pin "1") (pinfunction "1_1") (pintype "passive"))
    )
    (net (code "215") (name "unconnected-(IC1-PA0-Pad14)") (class "Default")
      (node (ref "IC1") (pin "14") (pinfunction "PA0_14") (pintype "bidirectional"))
    )
    (net (code "216") (name "unconnected-(IC1-PB2-Pad28)") (class "Default")
      (node (ref "IC1") (pin "28") (pinfunction "PB2_28") (pintype "bidirectional"))
    )
    (net (code "217") (name "unconnected-(IC1-PC4-Pad24)") (class "Default")
      (node (ref "IC1") (pin "24") (pinfunction "PC4_24") (pintype "bidirectional"))
    )
    (net (code "218") (name "unconnected-(IC1-PC5-Pad25)") (class "Default")
      (node (ref "IC1") (pin "25") (pinfunction "PC5_25") (pintype "bidirectional"))
    )
    (net (code "219") (name "unconnected-(IC1-PF4-Pad18)") (class "Default")
      (node (ref "IC1") (pin "18") (pinfunction "PF4_18") (pintype "bidirectional"))
    )
    (net (code "220") (name "unconnected-(J2-PadMH1)") (class "Default")
      (node (ref "J2") (pin "MH1") (pinfunction "MH1_MH1") (pintype "bidirectional"))
    )
    (net (code "221") (name "unconnected-(J2-PadMH2)") (class "Default")
      (node (ref "J2") (pin "MH2") (pinfunction "MH2_MH2") (pintype "bidirectional"))
    )
    (net (code "222") (name "unconnected-(J2-PadMH3)") (class "Default")
      (node (ref "J2") (pin "MH3") (pinfunction "MH3_MH3") (pintype "bidirectional"))
    )
    (net (code "223") (name "unconnected-(J2-PadMH4)") (class "Default")
      (node (ref "J2") (pin "MH4") (pinfunction "MH4_MH4") (pintype "bidirectional"))
    )
    (net (code "224") (name "unconnected-(S2-NO_2-PadB1)") (class "Default")
      (node (ref "S2") (pin "B1") (pinfunction "NO_2_B1") (pintype "bidirectional"))
    )
  )
)
